# EagleIO.net
KiCad netlist of a schematic drawn in EAGLE
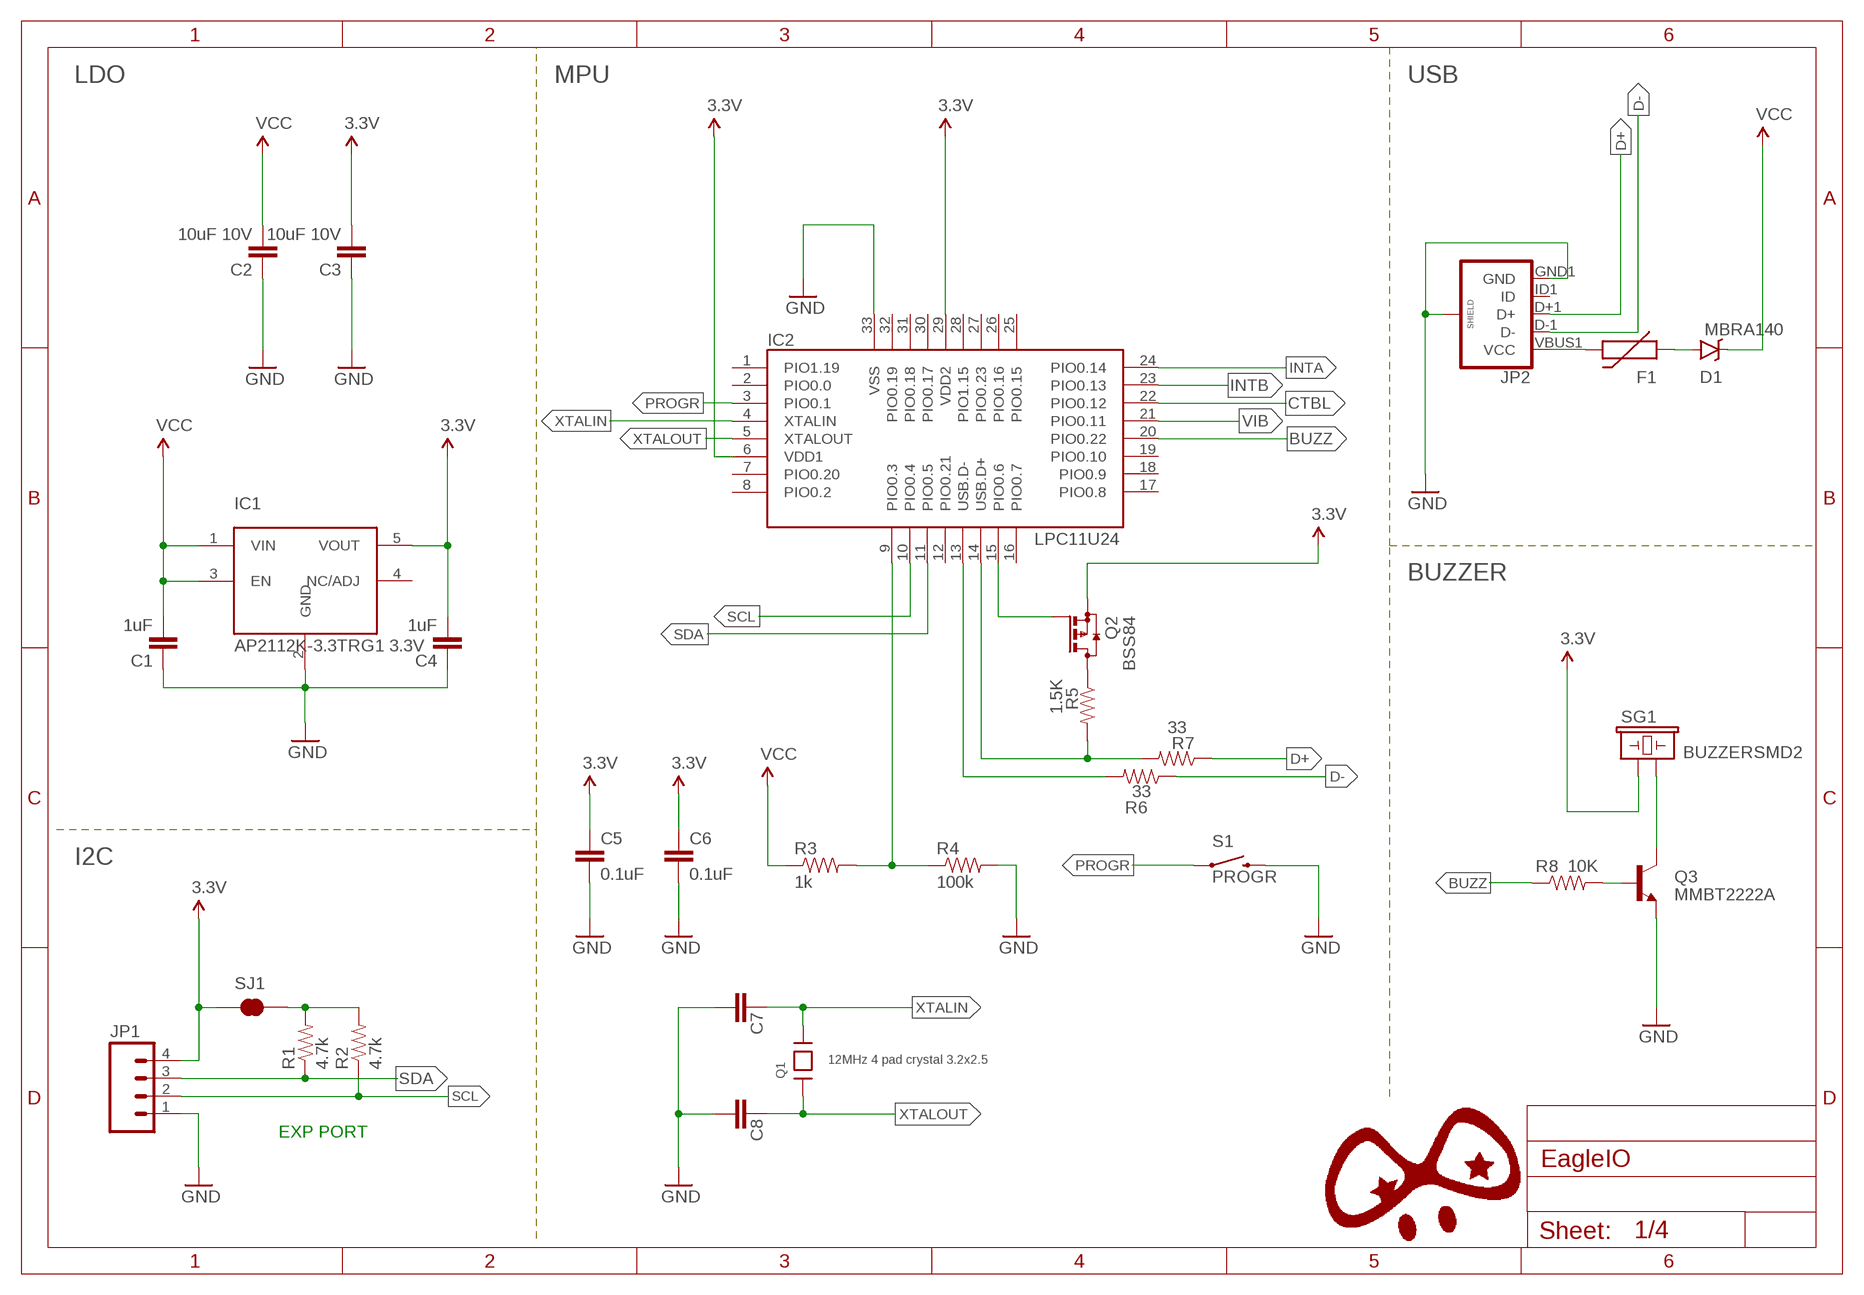
[diagram p0: schematic, sheet 1]
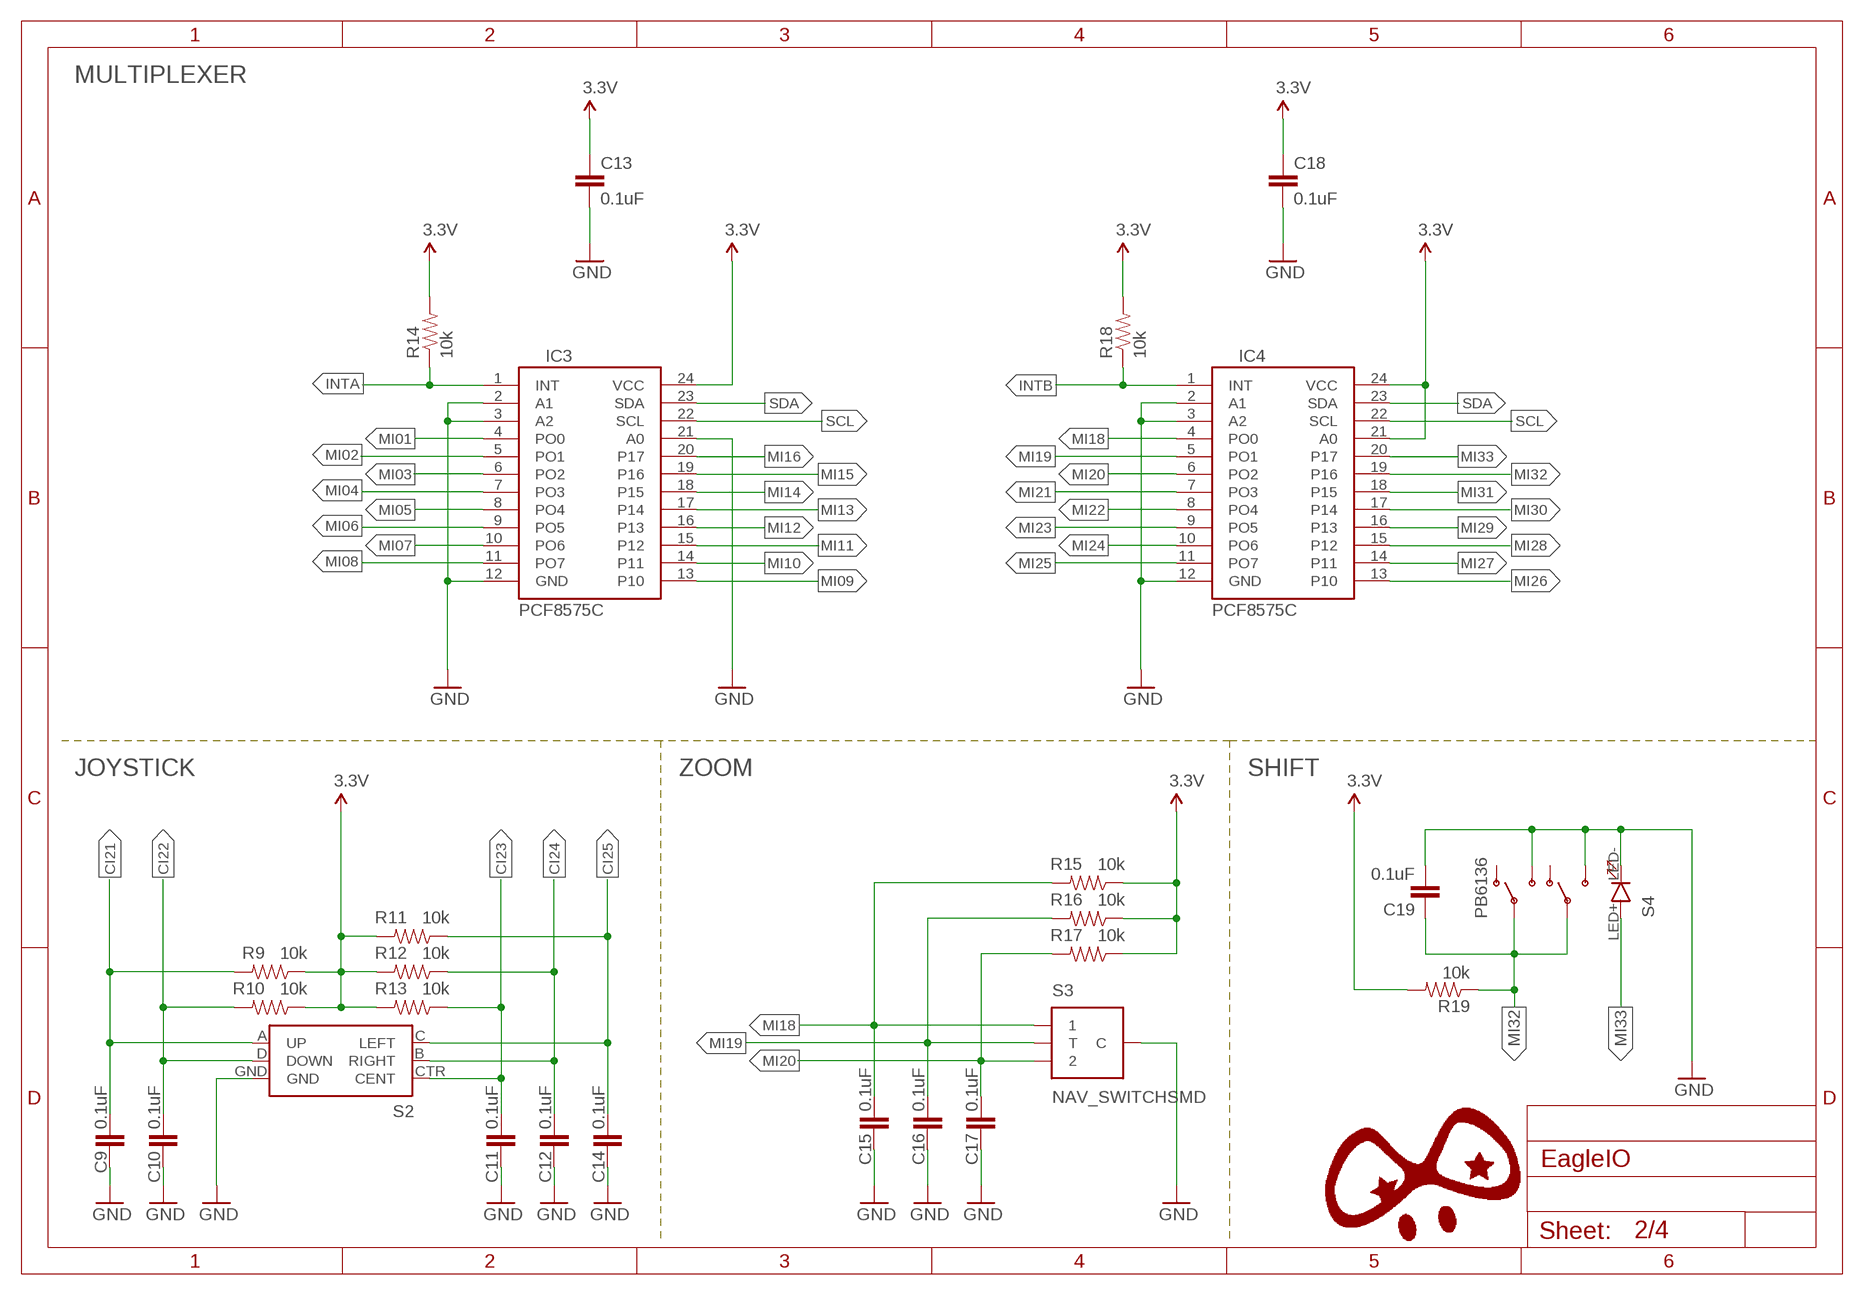
[diagram p1: schematic, sheet 2]
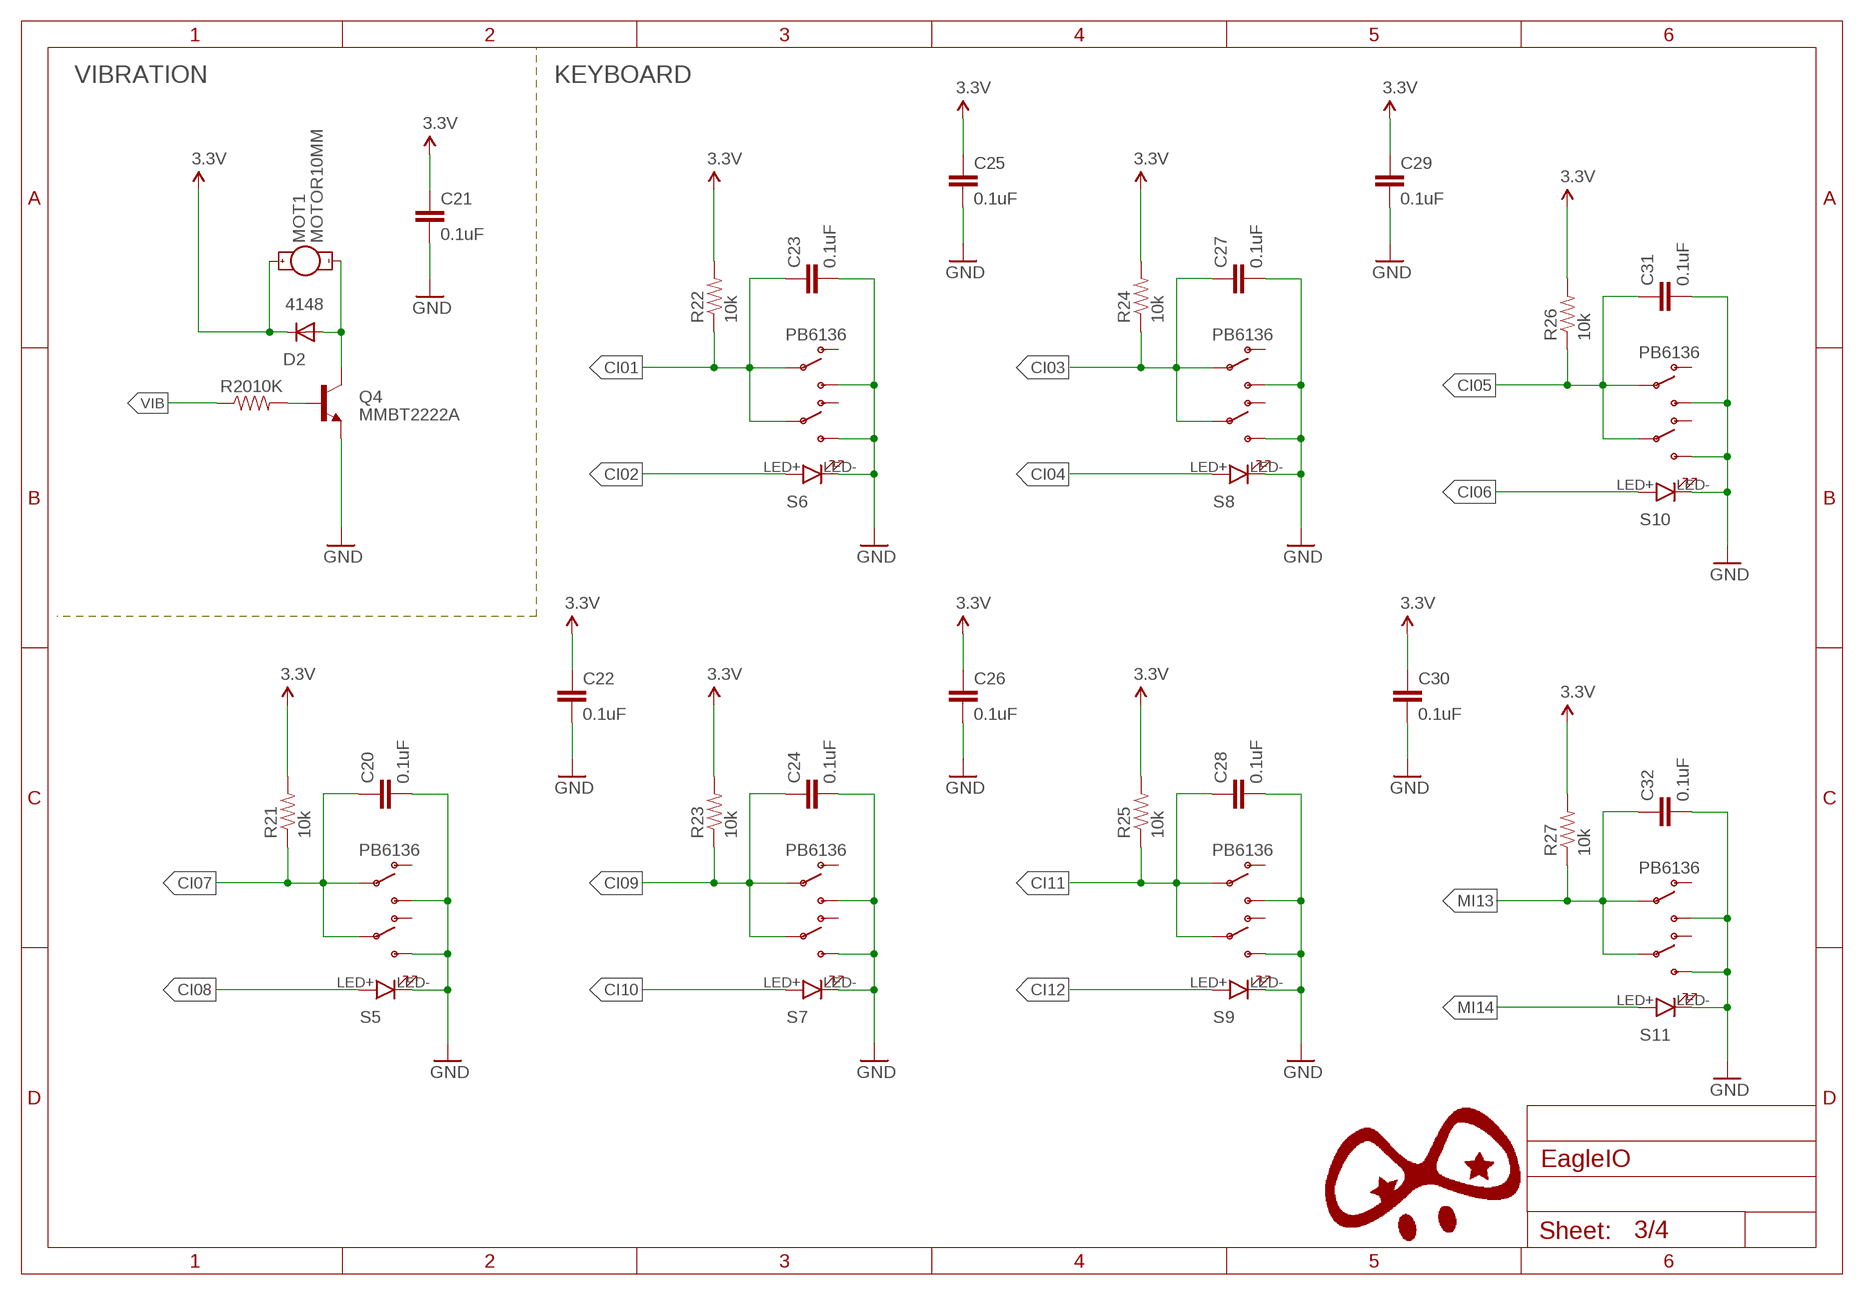
[diagram p2: schematic, sheet 3]
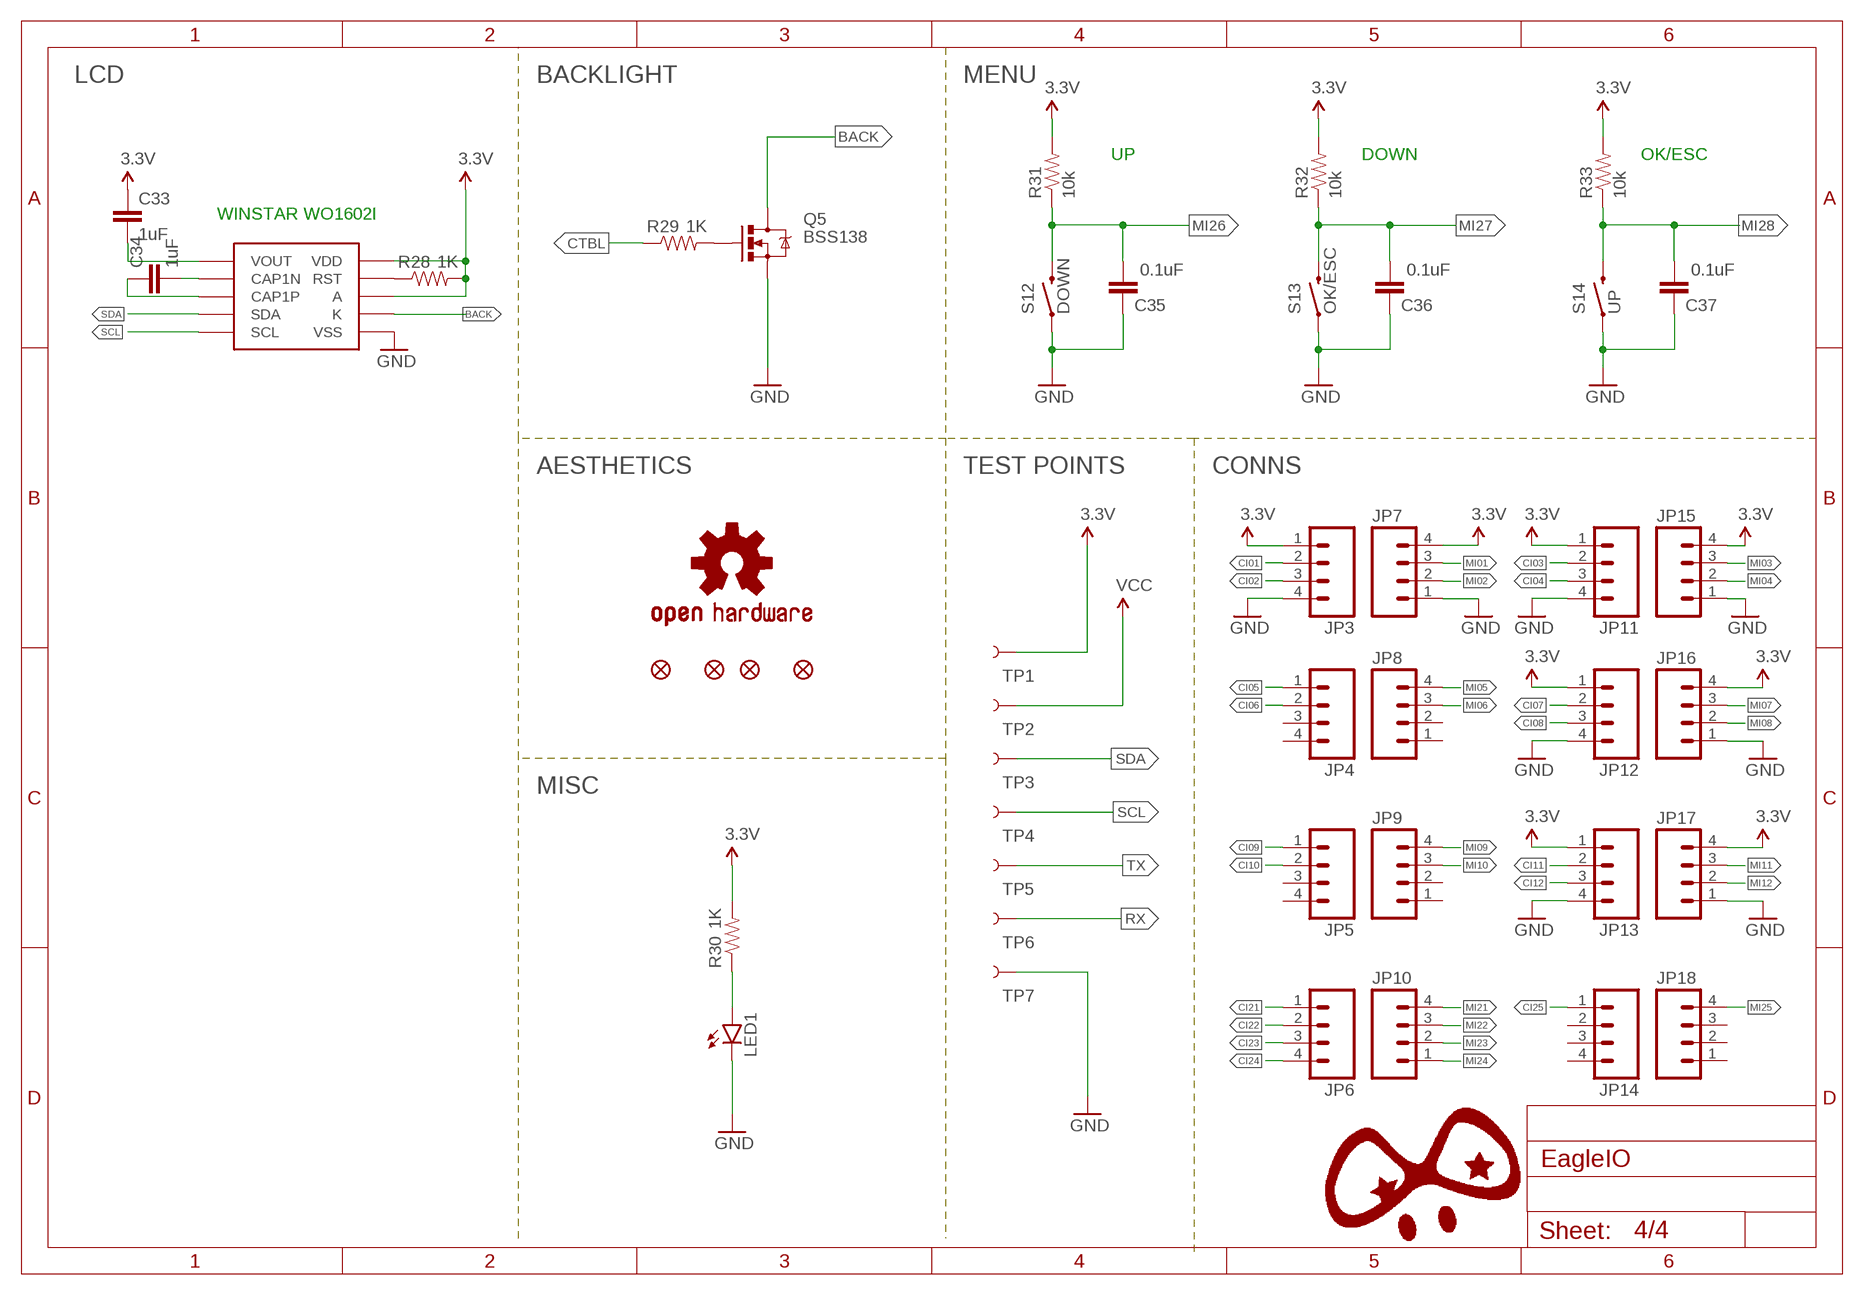
[diagram p3: schematic, sheet 4]

(export (version "E")
  (design (tool "Eeschema 10.0.6"))
  (components
    (comp (ref "C20")
      (value "0.1uF")
      (footprint "eagle-import:0402-CAP")
      (libsource (lib "eagle-import") (part "CAP0402-CAP"))
    )
    (comp (ref "C21")
      (value "0.1uF")
      (footprint "eagle-import:0402-CAP")
      (libsource (lib "eagle-import") (part "CAP0402-CAP"))
    )
    (comp (ref "C22")
      (value "0.1uF")
      (footprint "eagle-import:0402-CAP")
      (libsource (lib "eagle-import") (part "CAP0402-CAP"))
    )
    (comp (ref "C23")
      (value "0.1uF")
      (footprint "eagle-import:0402-CAP")
      (libsource (lib "eagle-import") (part "CAP0402-CAP"))
    )
    (comp (ref "C24")
      (value "0.1uF")
      (footprint "eagle-import:0402-CAP")
      (libsource (lib "eagle-import") (part "CAP0402-CAP"))
    )
    (comp (ref "C25")
      (value "0.1uF")
      (footprint "eagle-import:0402-CAP")
      (libsource (lib "eagle-import") (part "CAP0402-CAP"))
    )
    (comp (ref "C26")
      (value "0.1uF")
      (footprint "eagle-import:0402-CAP")
      (libsource (lib "eagle-import") (part "CAP0402-CAP"))
    )
    (comp (ref "C27")
      (value "0.1uF")
      (footprint "eagle-import:0402-CAP")
      (libsource (lib "eagle-import") (part "CAP0402-CAP"))
    )
    (comp (ref "C28")
      (value "0.1uF")
      (footprint "eagle-import:0402-CAP")
      (libsource (lib "eagle-import") (part "CAP0402-CAP"))
    )
    (comp (ref "C29")
      (value "0.1uF")
      (footprint "eagle-import:0402-CAP")
      (libsource (lib "eagle-import") (part "CAP0402-CAP"))
    )
    (comp (ref "C30")
      (value "0.1uF")
      (footprint "eagle-import:0402-CAP")
      (libsource (lib "eagle-import") (part "CAP0402-CAP"))
    )
    (comp (ref "C31")
      (value "0.1uF")
      (footprint "eagle-import:0402-CAP")
      (libsource (lib "eagle-import") (part "CAP0402-CAP"))
    )
    (comp (ref "C32")
      (value "0.1uF")
      (footprint "eagle-import:0402-CAP")
      (libsource (lib "eagle-import") (part "CAP0402-CAP"))
    )
    (comp (ref "D2")
      (value "4148")
      (footprint "eagle-import:MINIMELF")
      (libsource (lib "eagle-import") (part "DIODE-MINIMELF"))
    )
    (comp (ref "MOT1")
      (value "MOTOR10MM")
      (footprint "eagle-import:VIBE-MOTOR-10MM")
      (libsource (lib "eagle-import") (part "MOTOR10MM"))
    )
    (comp (ref "Q4")
      (value "MMBT2222A")
      (footprint "eagle-import:SOT23-3")
      (libsource (lib "eagle-import") (part "TRANSISTOR_NPNMMBT2222A"))
    )
    (comp (ref "R20")
      (value "10K")
      (footprint "eagle-import:0402-RES")
      (libsource (lib "eagle-import") (part "RESISTOR0402-RES"))
    )
    (comp (ref "R21")
      (value "10k")
      (footprint "eagle-import:0402-RES")
      (libsource (lib "eagle-import") (part "SparkFun-Passives_RESISTOR0402-RES"))
    )
    (comp (ref "R22")
      (value "10k")
      (footprint "eagle-import:0402-RES")
      (libsource (lib "eagle-import") (part "SparkFun-Passives_RESISTOR0402-RES"))
    )
    (comp (ref "R23")
      (value "10k")
      (footprint "eagle-import:0402-RES")
      (libsource (lib "eagle-import") (part "SparkFun-Passives_RESISTOR0402-RES"))
    )
    (comp (ref "R24")
      (value "10k")
      (footprint "eagle-import:0402-RES")
      (libsource (lib "eagle-import") (part "SparkFun-Passives_RESISTOR0402-RES"))
    )
    (comp (ref "R25")
      (value "10k")
      (footprint "eagle-import:0402-RES")
      (libsource (lib "eagle-import") (part "SparkFun-Passives_RESISTOR0402-RES"))
    )
    (comp (ref "R26")
      (value "10k")
      (footprint "eagle-import:0402-RES")
      (libsource (lib "eagle-import") (part "SparkFun-Passives_RESISTOR0402-RES"))
    )
    (comp (ref "R27")
      (value "10k")
      (footprint "eagle-import:0402-RES")
      (libsource (lib "eagle-import") (part "SparkFun-Passives_RESISTOR0402-RES"))
    )
    (comp (ref "S5")
      (value "PB6136")
      (footprint "eagle-import:PB6136")
      (libsource (lib "eagle-import") (part "PB6136"))
    )
    (comp (ref "S6")
      (value "PB6136")
      (footprint "eagle-import:PB6136")
      (libsource (lib "eagle-import") (part "PB6136"))
    )
    (comp (ref "S7")
      (value "PB6136")
      (footprint "eagle-import:PB6136")
      (libsource (lib "eagle-import") (part "PB6136"))
    )
    (comp (ref "S8")
      (value "PB6136")
      (footprint "eagle-import:PB6136")
      (libsource (lib "eagle-import") (part "PB6136"))
    )
    (comp (ref "S9")
      (value "PB6136")
      (footprint "eagle-import:PB6136")
      (libsource (lib "eagle-import") (part "PB6136"))
    )
    (comp (ref "S10")
      (value "PB6136")
      (footprint "eagle-import:PB6136")
      (libsource (lib "eagle-import") (part "PB6136"))
    )
    (comp (ref "S11")
      (value "PB6136")
      (footprint "eagle-import:PB6136")
      (libsource (lib "eagle-import") (part "PB6136"))
    )
    (comp (ref "C9")
      (value "0.1uF")
      (footprint "eagle-import:0402-CAP")
      (libsource (lib "eagle-import") (part "CAP0402-CAP"))
    )
    (comp (ref "C10")
      (value "0.1uF")
      (footprint "eagle-import:0402-CAP")
      (libsource (lib "eagle-import") (part "CAP0402-CAP"))
    )
    (comp (ref "C11")
      (value "0.1uF")
      (footprint "eagle-import:0402-CAP")
      (libsource (lib "eagle-import") (part "CAP0402-CAP"))
    )
    (comp (ref "C12")
      (value "0.1uF")
      (footprint "eagle-import:0402-CAP")
      (libsource (lib "eagle-import") (part "CAP0402-CAP"))
    )
    (comp (ref "C13")
      (value "0.1uF")
      (footprint "eagle-import:0402-CAP")
      (libsource (lib "eagle-import") (part "CAP0402-CAP"))
    )
    (comp (ref "C14")
      (value "0.1uF")
      (footprint "eagle-import:0402-CAP")
      (libsource (lib "eagle-import") (part "CAP0402-CAP"))
    )
    (comp (ref "C15")
      (value "0.1uF")
      (footprint "eagle-import:0402-CAP")
      (libsource (lib "eagle-import") (part "CAP0402-CAP"))
    )
    (comp (ref "C16")
      (value "0.1uF")
      (footprint "eagle-import:0402-CAP")
      (libsource (lib "eagle-import") (part "CAP0402-CAP"))
    )
    (comp (ref "C17")
      (value "0.1uF")
      (footprint "eagle-import:0402-CAP")
      (libsource (lib "eagle-import") (part "CAP0402-CAP"))
    )
    (comp (ref "C18")
      (value "0.1uF")
      (footprint "eagle-import:0402-CAP")
      (libsource (lib "eagle-import") (part "CAP0402-CAP"))
    )
    (comp (ref "C19")
      (value "0.1uF")
      (footprint "eagle-import:0402-CAP")
      (libsource (lib "eagle-import") (part "CAP0402-CAP"))
    )
    (comp (ref "IC3")
      (value "PCF8575C")
      (footprint "eagle-import:SO-24DW")
      (libsource (lib "eagle-import") (part "PCF8575C"))
    )
    (comp (ref "IC4")
      (value "PCF8575C")
      (footprint "eagle-import:SO-24DW")
      (libsource (lib "eagle-import") (part "PCF8575C"))
    )
    (comp (ref "R9")
      (value "10k")
      (footprint "eagle-import:0402-RES")
      (libsource (lib "eagle-import") (part "SparkFun-Passives_RESISTOR0402-RES"))
    )
    (comp (ref "R10")
      (value "10k")
      (footprint "eagle-import:0402-RES")
      (libsource (lib "eagle-import") (part "SparkFun-Passives_RESISTOR0402-RES"))
    )
    (comp (ref "R11")
      (value "10k")
      (footprint "eagle-import:0402-RES")
      (libsource (lib "eagle-import") (part "SparkFun-Passives_RESISTOR0402-RES"))
    )
    (comp (ref "R12")
      (value "10k")
      (footprint "eagle-import:0402-RES")
      (libsource (lib "eagle-import") (part "SparkFun-Passives_RESISTOR0402-RES"))
    )
    (comp (ref "R13")
      (value "10k")
      (footprint "eagle-import:0402-RES")
      (libsource (lib "eagle-import") (part "SparkFun-Passives_RESISTOR0402-RES"))
    )
    (comp (ref "R14")
      (value "10k")
      (footprint "eagle-import:0402-RES")
      (libsource (lib "eagle-import") (part "SparkFun-Passives_RESISTOR0402-RES"))
    )
    (comp (ref "R15")
      (value "10k")
      (footprint "eagle-import:0402-RES")
      (libsource (lib "eagle-import") (part "SparkFun-Passives_RESISTOR0402-RES"))
    )
    (comp (ref "R16")
      (value "10k")
      (footprint "eagle-import:0402-RES")
      (libsource (lib "eagle-import") (part "SparkFun-Passives_RESISTOR0402-RES"))
    )
    (comp (ref "R17")
      (value "10k")
      (footprint "eagle-import:0402-RES")
      (libsource (lib "eagle-import") (part "SparkFun-Passives_RESISTOR0402-RES"))
    )
    (comp (ref "R18")
      (value "10k")
      (footprint "eagle-import:0402-RES")
      (libsource (lib "eagle-import") (part "SparkFun-Passives_RESISTOR0402-RES"))
    )
    (comp (ref "R19")
      (value "10k")
      (footprint "eagle-import:0402-RES")
      (libsource (lib "eagle-import") (part "SparkFun-Passives_RESISTOR0402-RES"))
    )
    (comp (ref "S2")
      (value "JOYSTICK_MINI")
      (footprint "eagle-import:JOYSTICK_MINI")
      (libsource (lib "eagle-import") (part "JOYSTICK_MINI"))
    )
    (comp (ref "S3")
      (value "NAV_SWITCHSMD")
      (footprint "eagle-import:NAV_SWITCH")
      (libsource (lib "eagle-import") (part "NAV_SWITCHSMD"))
    )
    (comp (ref "S4")
      (value "PB6136")
      (footprint "eagle-import:PB6136")
      (libsource (lib "eagle-import") (part "PB6136"))
    )
    (comp (ref "C33")
      (value "1uF")
      (footprint "eagle-import:0402-CAP")
      (libsource (lib "eagle-import") (part "CAP0402-CAP"))
    )
    (comp (ref "C34")
      (value "1uF")
      (footprint "eagle-import:0402-CAP")
      (libsource (lib "eagle-import") (part "CAP0402-CAP"))
    )
    (comp (ref "C35")
      (value "0.1uF")
      (footprint "eagle-import:0402-CAP")
      (libsource (lib "eagle-import") (part "CAP0402-CAP"))
    )
    (comp (ref "C36")
      (value "0.1uF")
      (footprint "eagle-import:0402-CAP")
      (libsource (lib "eagle-import") (part "CAP0402-CAP"))
    )
    (comp (ref "C37")
      (value "0.1uF")
      (footprint "eagle-import:0402-CAP")
      (libsource (lib "eagle-import") (part "CAP0402-CAP"))
    )
    (comp (ref "FID1")
      (value "FIDUCIAL1X2")
      (footprint "eagle-import:FIDUCIAL-1X2")
      (libsource (lib "eagle-import") (part "FIDUCIAL1X2"))
    )
    (comp (ref "FID2")
      (value "FIDUCIAL1X2")
      (footprint "eagle-import:FIDUCIAL-1X2")
      (libsource (lib "eagle-import") (part "FIDUCIAL1X2"))
    )
    (comp (ref "FID3")
      (value "FIDUCIAL1X2")
      (footprint "eagle-import:FIDUCIAL-1X2")
      (libsource (lib "eagle-import") (part "FIDUCIAL1X2"))
    )
    (comp (ref "FID4")
      (value "FIDUCIAL1X2")
      (footprint "eagle-import:FIDUCIAL-1X2")
      (libsource (lib "eagle-import") (part "FIDUCIAL1X2"))
    )
    (comp (ref "JP3")
      (value "M041.27MM")
      (footprint "eagle-import:1X04-1.27MM")
      (libsource (lib "eagle-import") (part "M041.27MM"))
    )
    (comp (ref "JP4")
      (value "M041.27MM")
      (footprint "eagle-import:1X04-1.27MM")
      (libsource (lib "eagle-import") (part "M041.27MM"))
    )
    (comp (ref "JP5")
      (value "M041.27MM")
      (footprint "eagle-import:1X04-1.27MM")
      (libsource (lib "eagle-import") (part "M041.27MM"))
    )
    (comp (ref "JP6")
      (value "M041.27MM")
      (footprint "eagle-import:1X04-1.27MM")
      (libsource (lib "eagle-import") (part "M041.27MM"))
    )
    (comp (ref "JP7")
      (value "M041.27MM")
      (footprint "eagle-import:1X04-1.27MM")
      (libsource (lib "eagle-import") (part "M041.27MM"))
    )
    (comp (ref "JP8")
      (value "M041.27MM")
      (footprint "eagle-import:1X04-1.27MM")
      (libsource (lib "eagle-import") (part "M041.27MM"))
    )
    (comp (ref "JP9")
      (value "M041.27MM")
      (footprint "eagle-import:1X04-1.27MM")
      (libsource (lib "eagle-import") (part "M041.27MM"))
    )
    (comp (ref "JP10")
      (value "M041.27MM")
      (footprint "eagle-import:1X04-1.27MM")
      (libsource (lib "eagle-import") (part "M041.27MM"))
    )
    (comp (ref "JP11")
      (value "M041.27MM")
      (footprint "eagle-import:1X04-1.27MM")
      (libsource (lib "eagle-import") (part "M041.27MM"))
    )
    (comp (ref "JP12")
      (value "M041.27MM")
      (footprint "eagle-import:1X04-1.27MM")
      (libsource (lib "eagle-import") (part "M041.27MM"))
    )
    (comp (ref "JP13")
      (value "M041.27MM")
      (footprint "eagle-import:1X04-1.27MM")
      (libsource (lib "eagle-import") (part "M041.27MM"))
    )
    (comp (ref "JP14")
      (value "M041.27MM")
      (footprint "eagle-import:1X04-1.27MM")
      (libsource (lib "eagle-import") (part "M041.27MM"))
    )
    (comp (ref "JP15")
      (value "M041.27MM")
      (footprint "eagle-import:1X04-1.27MM")
      (libsource (lib "eagle-import") (part "M041.27MM"))
    )
    (comp (ref "JP16")
      (value "M041.27MM")
      (footprint "eagle-import:1X04-1.27MM")
      (libsource (lib "eagle-import") (part "M041.27MM"))
    )
    (comp (ref "JP17")
      (value "M041.27MM")
      (footprint "eagle-import:1X04-1.27MM")
      (libsource (lib "eagle-import") (part "M041.27MM"))
    )
    (comp (ref "JP18")
      (value "M041.27MM")
      (footprint "eagle-import:1X04-1.27MM")
      (libsource (lib "eagle-import") (part "M041.27MM"))
    )
    (comp (ref "LCD1")
      (value "WINSTAR_WO1602I")
      (footprint "eagle-import:WINSTAR_WO1602I")
      (libsource (lib "eagle-import") (part "WINSTAR_WO1602I"))
    )
    (comp (ref "LED1")
      (value "LED0603")
      (footprint "eagle-import:LED-0603")
      (libsource (lib "eagle-import") (part "LED0603"))
    )
    (comp (ref "LOGO1")
      (value "OSHW-LOGOS")
      (footprint "eagle-import:OSHW-LOGO-S")
      (libsource (lib "eagle-import") (part "OSHW-LOGOS"))
    )
    (comp (ref "Q5")
      (value "BSS138")
      (footprint "eagle-import:SOT323")
      (libsource (lib "eagle-import") (part "MOSFET-NCHANNEL2N7002PW"))
    )
    (comp (ref "R28")
      (value "1K")
      (footprint "eagle-import:0402-RES")
      (libsource (lib "eagle-import") (part "RESISTOR0402-RES"))
    )
    (comp (ref "R29")
      (value "1K")
      (footprint "eagle-import:0402-RES")
      (libsource (lib "eagle-import") (part "RESISTOR0402-RES"))
    )
    (comp (ref "R30")
      (value "1K")
      (footprint "eagle-import:0402-RES")
      (libsource (lib "eagle-import") (part "RESISTOR0402-RES"))
    )
    (comp (ref "R31")
      (value "10k")
      (footprint "eagle-import:0402-RES")
      (libsource (lib "eagle-import") (part "SparkFun-Passives_RESISTOR0402-RES"))
    )
    (comp (ref "R32")
      (value "10k")
      (footprint "eagle-import:0402-RES")
      (libsource (lib "eagle-import") (part "SparkFun-Passives_RESISTOR0402-RES"))
    )
    (comp (ref "R33")
      (value "10k")
      (footprint "eagle-import:0402-RES")
      (libsource (lib "eagle-import") (part "SparkFun-Passives_RESISTOR0402-RES"))
    )
    (comp (ref "S12")
      (value "DOWN")
      (footprint "eagle-import:TACTILE-SWITCH-1101NE")
      (libsource (lib "eagle-import") (part "SWITCH-MOMENTARY-2SMD-1101NE"))
    )
    (comp (ref "S13")
      (value "OK/ESC")
      (footprint "eagle-import:TACTILE-SWITCH-1101NE")
      (libsource (lib "eagle-import") (part "SWITCH-MOMENTARY-2SMD-1101NE"))
    )
    (comp (ref "S14")
      (value "UP")
      (footprint "eagle-import:TACTILE-SWITCH-1101NE")
      (libsource (lib "eagle-import") (part "SWITCH-MOMENTARY-2SMD-1101NE"))
    )
    (comp (ref "TP1")
      (value "TEST-POINT3X5")
      (footprint "eagle-import:PAD.03X.05")
      (libsource (lib "eagle-import") (part "TEST-POINT3X5"))
    )
    (comp (ref "TP2")
      (value "TEST-POINT3X5")
      (footprint "eagle-import:PAD.03X.05")
      (libsource (lib "eagle-import") (part "TEST-POINT3X5"))
    )
    (comp (ref "TP3")
      (value "TEST-POINT3X5")
      (footprint "eagle-import:PAD.03X.05")
      (libsource (lib "eagle-import") (part "TEST-POINT3X5"))
    )
    (comp (ref "TP4")
      (value "TEST-POINT3X5")
      (footprint "eagle-import:PAD.03X.05")
      (libsource (lib "eagle-import") (part "TEST-POINT3X5"))
    )
    (comp (ref "TP5")
      (value "TEST-POINT3X5")
      (footprint "eagle-import:PAD.03X.05")
      (libsource (lib "eagle-import") (part "TEST-POINT3X5"))
    )
    (comp (ref "TP6")
      (value "TEST-POINT3X5")
      (footprint "eagle-import:PAD.03X.05")
      (libsource (lib "eagle-import") (part "TEST-POINT3X5"))
    )
    (comp (ref "TP7")
      (value "TEST-POINT3X5")
      (footprint "eagle-import:PAD.03X.05")
      (libsource (lib "eagle-import") (part "TEST-POINT3X5"))
    )
    (comp (ref "C1")
      (value "1uF")
      (footprint "eagle-import:0402-CAP")
      (libsource (lib "eagle-import") (part "CAP0402-CAP"))
    )
    (comp (ref "C2")
      (value "10uF 10V")
      (footprint "eagle-import:0402-CAP")
      (libsource (lib "eagle-import") (part "CAP0402-CAP"))
    )
    (comp (ref "C3")
      (value "10uF 10V")
      (footprint "eagle-import:0402-CAP")
      (libsource (lib "eagle-import") (part "CAP0402-CAP"))
    )
    (comp (ref "C4")
      (value "1uF")
      (footprint "eagle-import:0402-CAP")
      (libsource (lib "eagle-import") (part "CAP0402-CAP"))
    )
    (comp (ref "C5")
      (value "0.1uF")
      (footprint "eagle-import:0402-CAP")
      (libsource (lib "eagle-import") (part "CAP0402-CAP"))
    )
    (comp (ref "C6")
      (value "0.1uF")
      (footprint "eagle-import:0402-CAP")
      (libsource (lib "eagle-import") (part "CAP0402-CAP"))
    )
    (comp (ref "C7")
      (value "27pF")
      (footprint "eagle-import:0402-CAP")
      (libsource (lib "eagle-import") (part "CAP0402-CAP"))
    )
    (comp (ref "C8")
      (value "27pF")
      (footprint "eagle-import:0402-CAP")
      (libsource (lib "eagle-import") (part "CAP0402-CAP"))
    )
    (comp (ref "D1")
      (value "MBRA140")
      (footprint "eagle-import:SMA-DIODE")
      (libsource (lib "eagle-import") (part "MBRA140"))
    )
    (comp (ref "F1")
      (value "PTC0603")
      (footprint "eagle-import:0603")
      (libsource (lib "eagle-import") (part "PTC0603"))
    )
    (comp (ref "IC1")
      (value "AP2112K-3.3TRG1 3.3V")
      (footprint "eagle-import:SOT23-5")
      (libsource (lib "eagle-import") (part "5PIN_REG"))
    )
    (comp (ref "IC2")
      (value "LPC11U24")
      (footprint "eagle-import:HVQFN33_5X5MM")
      (libsource (lib "eagle-import") (part "LPC11U2X_HVQFN33(5X5)"))
    )
    (comp (ref "JP1")
      (value "M04LONGPADS")
      (footprint "eagle-import:1X04_LONGPADS")
      (libsource (lib "eagle-import") (part "M04LONGPADS"))
    )
    (comp (ref "JP2")
      (value "USB_MICROB_PLUGCONN-11752")
      (footprint "eagle-import:USB-B-MICRO-SMD_V03")
      (libsource (lib "eagle-import") (part "USB_MICROB_PLUGCONN-11752"))
    )
    (comp (ref "Q1")
      (value "12MHz 4 pad crystal 3.2x2.5")
      (footprint "eagle-import:CRYSTAL_3.2X2.5")
      (libsource (lib "eagle-import") (part "CRYSTAL3.2X2.5"))
    )
    (comp (ref "Q2")
      (value "BSS84")
      (footprint "eagle-import:SOT23")
      (libsource (lib "eagle-import") (part "BSS84"))
    )
    (comp (ref "Q3")
      (value "MMBT2222A")
      (footprint "eagle-import:SOT23-3")
      (libsource (lib "eagle-import") (part "TRANSISTOR_NPNMMBT2222A"))
    )
    (comp (ref "R1")
      (value "4.7k")
      (footprint "eagle-import:0402-RES")
      (libsource (lib "eagle-import") (part "SparkFun-Passives_RESISTOR0402-RES"))
    )
    (comp (ref "R2")
      (value "4.7k")
      (footprint "eagle-import:0402-RES")
      (libsource (lib "eagle-import") (part "SparkFun-Passives_RESISTOR0402-RES"))
    )
    (comp (ref "R3")
      (value "1k")
      (footprint "eagle-import:0402-RES")
      (libsource (lib "eagle-import") (part "SparkFun-Passives_RESISTOR0402-RES"))
    )
    (comp (ref "R4")
      (value "100k")
      (footprint "eagle-import:0402-RES")
      (libsource (lib "eagle-import") (part "SparkFun-Passives_RESISTOR0402-RES"))
    )
    (comp (ref "R5")
      (value "1.5K")
      (footprint "eagle-import:0402-RES")
      (libsource (lib "eagle-import") (part "SparkFun-Passives_RESISTOR0402-RES"))
    )
    (comp (ref "R6")
      (value "33")
      (footprint "eagle-import:0402-RES")
      (libsource (lib "eagle-import") (part "SparkFun-Passives_RESISTOR0402-RES"))
    )
    (comp (ref "R7")
      (value "33")
      (footprint "eagle-import:0402-RES")
      (libsource (lib "eagle-import") (part "SparkFun-Passives_RESISTOR0402-RES"))
    )
    (comp (ref "R8")
      (value "10K")
      (footprint "eagle-import:0402-RES")
      (libsource (lib "eagle-import") (part "RESISTOR0402-RES"))
    )
    (comp (ref "S1")
      (value "PROGR")
      (footprint "eagle-import:TACTILE-SWITCH-1101NE")
      (libsource (lib "eagle-import") (part "SWITCH-MOMENTARY-2SMD-1101NE"))
    )
    (comp (ref "SG1")
      (value "BUZZERSMD2")
      (footprint "eagle-import:BUZZER-CCV")
      (libsource (lib "eagle-import") (part "BUZZERSMD2"))
    )
    (comp (ref "SJ1")
      (value "JUMPER-PAD-2-NC_BY_TRACE")
      (footprint "eagle-import:PAD-JUMPER-2-NC_BY_TRACE_YES_SILK")
      (libsource (lib "eagle-import") (part "JUMPER-PAD-2-NC_BY_TRACE"))
    )
  )
  (nets
    (net (code "1") (name "3.3V") (class "Default")
      (node (ref "C13") (pin "1") (pinfunction "1_1") (pintype "passive"))
      (node (ref "C18") (pin "1") (pinfunction "1_1") (pintype "passive"))
      (node (ref "C21") (pin "1") (pinfunction "1_1") (pintype "passive"))
      (node (ref "C22") (pin "1") (pinfunction "1_1") (pintype "passive"))
      (node (ref "C25") (pin "1") (pinfunction "1_1") (pintype "passive"))
      (node (ref "C26") (pin "1") (pinfunction "1_1") (pintype "passive"))
      (node (ref "C29") (pin "1") (pinfunction "1_1") (pintype "passive"))
      (node (ref "C3") (pin "2") (pinfunction "2_2") (pintype "passive"))
      (node (ref "C30") (pin "1") (pinfunction "1_1") (pintype "passive"))
      (node (ref "C33") (pin "1") (pinfunction "1_1") (pintype "passive"))
      (node (ref "C4") (pin "2") (pinfunction "2_2") (pintype "passive"))
      (node (ref "C5") (pin "1") (pinfunction "1_1") (pintype "passive"))
      (node (ref "C6") (pin "1") (pinfunction "1_1") (pintype "passive"))
      (node (ref "D2") (pin "C") (pinfunction "C_C") (pintype "passive"))
      (node (ref "IC1") (pin "5") (pinfunction "VOUT_5") (pintype "bidirectional"))
      (node (ref "IC2") (pin "29") (pinfunction "VDD2_29") (pintype "bidirectional"))
      (node (ref "IC2") (pin "6") (pinfunction "VDD1_6") (pintype "bidirectional"))
      (node (ref "IC3") (pin "24") (pinfunction "VCC_24") (pintype "bidirectional"))
      (node (ref "IC4") (pin "21") (pinfunction "A0_21") (pintype "bidirectional"))
      (node (ref "IC4") (pin "24") (pinfunction "VCC_24") (pintype "bidirectional"))
      (node (ref "JP1") (pin "4") (pinfunction "4_4") (pintype "passive"))
      (node (ref "JP11") (pin "1") (pinfunction "1_1") (pintype "passive"))
      (node (ref "JP12") (pin "1") (pinfunction "1_1") (pintype "passive"))
      (node (ref "JP13") (pin "1") (pinfunction "1_1") (pintype "passive"))
      (node (ref "JP15") (pin "4") (pinfunction "4_4") (pintype "passive"))
      (node (ref "JP16") (pin "4") (pinfunction "4_4") (pintype "passive"))
      (node (ref "JP17") (pin "4") (pinfunction "4_4") (pintype "passive"))
      (node (ref "JP3") (pin "1") (pinfunction "1_1") (pintype "passive"))
      (node (ref "JP7") (pin "4") (pinfunction "4_4") (pintype "passive"))
      (node (ref "LCD1") (pin "AB") (pinfunction "A_AB") (pintype "bidirectional"))
      (node (ref "LCD1") (pin "AT") (pinfunction "A_AT") (pintype "bidirectional"))
      (node (ref "LCD1") (pin "VDD") (pinfunction "VDD_VDD") (pintype "bidirectional"))
      (node (ref "MOT1") (pin "+") (pinfunction "+_+") (pintype "bidirectional"))
      (node (ref "Q2") (pin "2") (pinfunction "S_2") (pintype "passive"))
      (node (ref "R10") (pin "1") (pinfunction "1_1") (pintype "passive"))
      (node (ref "R11") (pin "2") (pinfunction "2_2") (pintype "passive"))
      (node (ref "R12") (pin "2") (pinfunction "2_2") (pintype "passive"))
      (node (ref "R13") (pin "2") (pinfunction "2_2") (pintype "passive"))
      (node (ref "R14") (pin "2") (pinfunction "2_2") (pintype "passive"))
      (node (ref "R15") (pin "1") (pinfunction "1_1") (pintype "passive"))
      (node (ref "R16") (pin "1") (pinfunction "1_1") (pintype "passive"))
      (node (ref "R17") (pin "1") (pinfunction "1_1") (pintype "passive"))
      (node (ref "R18") (pin "2") (pinfunction "2_2") (pintype "passive"))
      (node (ref "R19") (pin "2") (pinfunction "2_2") (pintype "passive"))
      (node (ref "R21") (pin "2") (pinfunction "2_2") (pintype "passive"))
      (node (ref "R22") (pin "2") (pinfunction "2_2") (pintype "passive"))
      (node (ref "R23") (pin "2") (pinfunction "2_2") (pintype "passive"))
      (node (ref "R24") (pin "2") (pinfunction "2_2") (pintype "passive"))
      (node (ref "R25") (pin "2") (pinfunction "2_2") (pintype "passive"))
      (node (ref "R26") (pin "2") (pinfunction "2_2") (pintype "passive"))
      (node (ref "R27") (pin "2") (pinfunction "2_2") (pintype "passive"))
      (node (ref "R28") (pin "2") (pinfunction "2_2") (pintype "passive"))
      (node (ref "R30") (pin "2") (pinfunction "2_2") (pintype "passive"))
      (node (ref "R31") (pin "2") (pinfunction "2_2") (pintype "passive"))
      (node (ref "R32") (pin "2") (pinfunction "2_2") (pintype "passive"))
      (node (ref "R33") (pin "2") (pinfunction "2_2") (pintype "passive"))
      (node (ref "R9") (pin "1") (pinfunction "1_1") (pintype "passive"))
      (node (ref "SG1") (pin "+") (pinfunction "1_+") (pintype "passive"))
      (node (ref "SJ1") (pin "1") (pinfunction "1_1") (pintype "passive"))
      (node (ref "TP1") (pin "P$1") (pinfunction "1_P$1") (pintype "bidirectional"))
    )
    (net (code "2") (name "BACK") (class "Default")
      (node (ref "LCD1") (pin "KB") (pinfunction "K_KB") (pintype "bidirectional"))
      (node (ref "LCD1") (pin "KT") (pinfunction "K_KT") (pintype "bidirectional"))
      (node (ref "Q5") (pin "3") (pinfunction "D_3") (pintype "passive"))
    )
    (net (code "3") (name "BUZZ") (class "Default")
      (node (ref "IC2") (pin "20") (pinfunction "PIO0.22_20") (pintype "bidirectional"))
      (node (ref "R8") (pin "1") (pinfunction "1_1") (pintype "passive"))
    )
    (net (code "4") (name "CI01") (class "Default")
      (node (ref "C23") (pin "1") (pinfunction "1_1") (pintype "passive"))
      (node (ref "JP3") (pin "2") (pinfunction "2_2") (pintype "passive"))
      (node (ref "R22") (pin "1") (pinfunction "1_1") (pintype "passive"))
      (node (ref "S6") (pin "C1") (pinfunction "P_C1") (pintype "passive"))
      (node (ref "S6") (pin "C2") (pinfunction "P1_C2") (pintype "passive"))
    )
    (net (code "5") (name "CI02") (class "Default")
      (node (ref "JP3") (pin "3") (pinfunction "3_3") (pintype "passive"))
      (node (ref "S6") (pin "LED+") (pinfunction "1_LED+") (pintype "passive"))
    )
    (net (code "6") (name "CI03") (class "Default")
      (node (ref "C27") (pin "1") (pinfunction "1_1") (pintype "passive"))
      (node (ref "JP11") (pin "2") (pinfunction "2_2") (pintype "passive"))
      (node (ref "R24") (pin "1") (pinfunction "1_1") (pintype "passive"))
      (node (ref "S8") (pin "C1") (pinfunction "P_C1") (pintype "passive"))
      (node (ref "S8") (pin "C2") (pinfunction "P1_C2") (pintype "passive"))
    )
    (net (code "7") (name "CI04") (class "Default")
      (node (ref "JP11") (pin "3") (pinfunction "3_3") (pintype "passive"))
      (node (ref "S8") (pin "LED+") (pinfunction "1_LED+") (pintype "passive"))
    )
    (net (code "8") (name "CI05") (class "Default")
      (node (ref "C31") (pin "1") (pinfunction "1_1") (pintype "passive"))
      (node (ref "JP4") (pin "1") (pinfunction "1_1") (pintype "passive"))
      (node (ref "R26") (pin "1") (pinfunction "1_1") (pintype "passive"))
      (node (ref "S10") (pin "C1") (pinfunction "P_C1") (pintype "passive"))
      (node (ref "S10") (pin "C2") (pinfunction "P1_C2") (pintype "passive"))
    )
    (net (code "9") (name "CI06") (class "Default")
      (node (ref "JP4") (pin "2") (pinfunction "2_2") (pintype "passive"))
      (node (ref "S10") (pin "LED+") (pinfunction "1_LED+") (pintype "passive"))
    )
    (net (code "10") (name "CI07") (class "Default")
      (node (ref "C20") (pin "1") (pinfunction "1_1") (pintype "passive"))
      (node (ref "JP12") (pin "2") (pinfunction "2_2") (pintype "passive"))
      (node (ref "R21") (pin "1") (pinfunction "1_1") (pintype "passive"))
      (node (ref "S5") (pin "C1") (pinfunction "P_C1") (pintype "passive"))
      (node (ref "S5") (pin "C2") (pinfunction "P1_C2") (pintype "passive"))
    )
    (net (code "11") (name "CI08") (class "Default")
      (node (ref "JP12") (pin "3") (pinfunction "3_3") (pintype "passive"))
      (node (ref "S5") (pin "LED+") (pinfunction "1_LED+") (pintype "passive"))
    )
    (net (code "12") (name "CI09") (class "Default")
      (node (ref "C24") (pin "1") (pinfunction "1_1") (pintype "passive"))
      (node (ref "JP5") (pin "1") (pinfunction "1_1") (pintype "passive"))
      (node (ref "R23") (pin "1") (pinfunction "1_1") (pintype "passive"))
      (node (ref "S7") (pin "C1") (pinfunction "P_C1") (pintype "passive"))
      (node (ref "S7") (pin "C2") (pinfunction "P1_C2") (pintype "passive"))
    )
    (net (code "13") (name "CI10") (class "Default")
      (node (ref "JP5") (pin "2") (pinfunction "2_2") (pintype "passive"))
      (node (ref "S7") (pin "LED+") (pinfunction "1_LED+") (pintype "passive"))
    )
    (net (code "14") (name "CI11") (class "Default")
      (node (ref "C28") (pin "1") (pinfunction "1_1") (pintype "passive"))
      (node (ref "JP13") (pin "2") (pinfunction "2_2") (pintype "passive"))
      (node (ref "R25") (pin "1") (pinfunction "1_1") (pintype "passive"))
      (node (ref "S9") (pin "C1") (pinfunction "P_C1") (pintype "passive"))
      (node (ref "S9") (pin "C2") (pinfunction "P1_C2") (pintype "passive"))
    )
    (net (code "15") (name "CI12") (class "Default")
      (node (ref "JP13") (pin "3") (pinfunction "3_3") (pintype "passive"))
      (node (ref "S9") (pin "LED+") (pinfunction "1_LED+") (pintype "passive"))
    )
    (net (code "16") (name "CI21") (class "Default")
      (node (ref "C9") (pin "2") (pinfunction "2_2") (pintype "passive"))
      (node (ref "JP6") (pin "1") (pinfunction "1_1") (pintype "passive"))
      (node (ref "R9") (pin "2") (pinfunction "2_2") (pintype "passive"))
      (node (ref "S2") (pin "A") (pinfunction "UP_A") (pintype "bidirectional"))
    )
    (net (code "17") (name "CI22") (class "Default")
      (node (ref "C10") (pin "2") (pinfunction "2_2") (pintype "passive"))
      (node (ref "JP6") (pin "2") (pinfunction "2_2") (pintype "passive"))
      (node (ref "R10") (pin "2") (pinfunction "2_2") (pintype "passive"))
      (node (ref "S2") (pin "D") (pinfunction "DOWN_D") (pintype "bidirectional"))
    )
    (net (code "18") (name "CI23") (class "Default")
      (node (ref "C11") (pin "2") (pinfunction "2_2") (pintype "passive"))
      (node (ref "JP6") (pin "3") (pinfunction "3_3") (pintype "passive"))
      (node (ref "R13") (pin "1") (pinfunction "1_1") (pintype "passive"))
      (node (ref "S2") (pin "CTR") (pinfunction "CENT_CTR") (pintype "bidirectional"))
    )
    (net (code "19") (name "CI24") (class "Default")
      (node (ref "C12") (pin "2") (pinfunction "2_2") (pintype "passive"))
      (node (ref "JP6") (pin "4") (pinfunction "4_4") (pintype "passive"))
      (node (ref "R12") (pin "1") (pinfunction "1_1") (pintype "passive"))
      (node (ref "S2") (pin "B") (pinfunction "RIGHT_B") (pintype "bidirectional"))
    )
    (net (code "20") (name "CI25") (class "Default")
      (node (ref "C14") (pin "2") (pinfunction "2_2") (pintype "passive"))
      (node (ref "JP14") (pin "1") (pinfunction "1_1") (pintype "passive"))
      (node (ref "R11") (pin "1") (pinfunction "1_1") (pintype "passive"))
      (node (ref "S2") (pin "C") (pinfunction "LEFT_C") (pintype "bidirectional"))
    )
    (net (code "21") (name "CTBL") (class "Default")
      (node (ref "IC2") (pin "22") (pinfunction "PIO0.12_22") (pintype "bidirectional"))
      (node (ref "R29") (pin "1") (pinfunction "1_1") (pintype "passive"))
    )
    (net (code "22") (name "D+") (class "Default")
      (node (ref "JP2") (pin "D+1") (pinfunction "D+_D+1") (pintype "bidirectional"))
      (node (ref "R7") (pin "1") (pinfunction "1_1") (pintype "passive"))
    )
    (net (code "23") (name "D-") (class "Default")
      (node (ref "JP2") (pin "D-1") (pinfunction "D-_D-1") (pintype "bidirectional"))
      (node (ref "R6") (pin "1") (pinfunction "1_1") (pintype "passive"))
    )
    (net (code "24") (name "GND") (class "Default")
      (node (ref "C1") (pin "1") (pinfunction "1_1") (pintype "passive"))
      (node (ref "C10") (pin "1") (pinfunction "1_1") (pintype "passive"))
      (node (ref "C11") (pin "1") (pinfunction "1_1") (pintype "passive"))
      (node (ref "C12") (pin "1") (pinfunction "1_1") (pintype "passive"))
      (node (ref "C13") (pin "2") (pinfunction "2_2") (pintype "passive"))
      (node (ref "C14") (pin "1") (pinfunction "1_1") (pintype "passive"))
      (node (ref "C15") (pin "1") (pinfunction "1_1") (pintype "passive"))
      (node (ref "C16") (pin "1") (pinfunction "1_1") (pintype "passive"))
      (node (ref "C17") (pin "1") (pinfunction "1_1") (pintype "passive"))
      (node (ref "C18") (pin "2") (pinfunction "2_2") (pintype "passive"))
      (node (ref "C19") (pin "2") (pinfunction "2_2") (pintype "passive"))
      (node (ref "C2") (pin "1") (pinfunction "1_1") (pintype "passive"))
      (node (ref "C20") (pin "2") (pinfunction "2_2") (pintype "passive"))
      (node (ref "C21") (pin "2") (pinfunction "2_2") (pintype "passive"))
      (node (ref "C22") (pin "2") (pinfunction "2_2") (pintype "passive"))
      (node (ref "C23") (pin "2") (pinfunction "2_2") (pintype "passive"))
      (node (ref "C24") (pin "2") (pinfunction "2_2") (pintype "passive"))
      (node (ref "C25") (pin "2") (pinfunction "2_2") (pintype "passive"))
      (node (ref "C26") (pin "2") (pinfunction "2_2") (pintype "passive"))
      (node (ref "C27") (pin "2") (pinfunction "2_2") (pintype "passive"))
      (node (ref "C28") (pin "2") (pinfunction "2_2") (pintype "passive"))
      (node (ref "C29") (pin "2") (pinfunction "2_2") (pintype "passive"))
      (node (ref "C3") (pin "1") (pinfunction "1_1") (pintype "passive"))
      (node (ref "C30") (pin "2") (pinfunction "2_2") (pintype "passive"))
      (node (ref "C31") (pin "2") (pinfunction "2_2") (pintype "passive"))
      (node (ref "C32") (pin "2") (pinfunction "2_2") (pintype "passive"))
      (node (ref "C35") (pin "1") (pinfunction "1_1") (pintype "passive"))
      (node (ref "C36") (pin "1") (pinfunction "1_1") (pintype "passive"))
      (node (ref "C37") (pin "1") (pinfunction "1_1") (pintype "passive"))
      (node (ref "C4") (pin "1") (pinfunction "1_1") (pintype "passive"))
      (node (ref "C5") (pin "2") (pinfunction "2_2") (pintype "passive"))
      (node (ref "C6") (pin "2") (pinfunction "2_2") (pintype "passive"))
      (node (ref "C7") (pin "2") (pinfunction "2_2") (pintype "passive"))
      (node (ref "C8") (pin "2") (pinfunction "2_2") (pintype "passive"))
      (node (ref "C9") (pin "1") (pinfunction "1_1") (pintype "passive"))
      (node (ref "IC1") (pin "2") (pinfunction "GND_2") (pintype "bidirectional"))
      (node (ref "IC2") (pin "33") (pinfunction "VSS_33") (pintype "bidirectional"))
      (node (ref "IC3") (pin "12") (pinfunction "GND_12") (pintype "bidirectional"))
      (node (ref "IC3") (pin "2") (pinfunction "A1_2") (pintype "bidirectional"))
      (node (ref "IC3") (pin "21") (pinfunction "A0_21") (pintype "bidirectional"))
      (node (ref "IC3") (pin "3") (pinfunction "A2_3") (pintype "bidirectional"))
      (node (ref "IC4") (pin "12") (pinfunction "GND_12") (pintype "bidirectional"))
      (node (ref "IC4") (pin "2") (pinfunction "A1_2") (pintype "bidirectional"))
      (node (ref "IC4") (pin "3") (pinfunction "A2_3") (pintype "bidirectional"))
      (node (ref "JP1") (pin "1") (pinfunction "1_1") (pintype "passive"))
      (node (ref "JP11") (pin "4") (pinfunction "4_4") (pintype "passive"))
      (node (ref "JP12") (pin "4") (pinfunction "4_4") (pintype "passive"))
      (node (ref "JP13") (pin "4") (pinfunction "4_4") (pintype "passive"))
      (node (ref "JP15") (pin "1") (pinfunction "1_1") (pintype "passive"))
      (node (ref "JP16") (pin "1") (pinfunction "1_1") (pintype "passive"))
      (node (ref "JP17") (pin "1") (pinfunction "1_1") (pintype "passive"))
      (node (ref "JP2") (pin "GND1") (pinfunction "GND_GND1") (pintype "bidirectional"))
      (node (ref "JP2") (pin "SHIELD1") (pinfunction "SHIELD_SHIELD1") (pintype "bidirectional"))
      (node (ref "JP2") (pin "SHIELD2") (pinfunction "SHIELD_SHIELD2") (pintype "bidirectional"))
      (node (ref "JP2") (pin "SHIELD3") (pinfunction "SHIELD_SHIELD3") (pintype "bidirectional"))
      (node (ref "JP3") (pin "4") (pinfunction "4_4") (pintype "passive"))
      (node (ref "JP7") (pin "1") (pinfunction "1_1") (pintype "passive"))
      (node (ref "LCD1") (pin "VSS") (pinfunction "VSS_VSS") (pintype "bidirectional"))
      (node (ref "LED1") (pin "C") (pinfunction "C_C") (pintype "passive"))
      (node (ref "Q3") (pin "2") (pinfunction "E_2") (pintype "passive"))
      (node (ref "Q4") (pin "2") (pinfunction "E_2") (pintype "passive"))
      (node (ref "Q5") (pin "2") (pinfunction "S_2") (pintype "passive"))
      (node (ref "R4") (pin "2") (pinfunction "2_2") (pintype "passive"))
      (node (ref "S1") (pin "2") (pinfunction "2_2") (pintype "passive"))
      (node (ref "S10") (pin "LED-") (pinfunction "2_LED-") (pintype "passive"))
      (node (ref "S10") (pin "NO1") (pinfunction "S_NO1") (pintype "passive"))
      (node (ref "S10") (pin "NO2") (pinfunction "S1_NO2") (pintype "passive"))
      (node (ref "S11") (pin "LED-") (pinfunction "2_LED-") (pintype "passive"))
      (node (ref "S11") (pin "NO1") (pinfunction "S_NO1") (pintype "passive"))
      (node (ref "S11") (pin "NO2") (pinfunction "S1_NO2") (pintype "passive"))
      (node (ref "S12") (pin "1") (pinfunction "1_1") (pintype "passive"))
      (node (ref "S13") (pin "1") (pinfunction "1_1") (pintype "passive"))
      (node (ref "S14") (pin "1") (pinfunction "1_1") (pintype "passive"))
      (node (ref "S2") (pin "GND") (pinfunction "GND_GND") (pintype "bidirectional"))
      (node (ref "S3") (pin "C") (pinfunction "C_C") (pintype "power_in"))
      (node (ref "S4") (pin "LED-") (pinfunction "2_LED-") (pintype "passive"))
      (node (ref "S4") (pin "NO1") (pinfunction "S_NO1") (pintype "passive"))
      (node (ref "S4") (pin "NO2") (pinfunction "S1_NO2") (pintype "passive"))
      (node (ref "S5") (pin "LED-") (pinfunction "2_LED-") (pintype "passive"))
      (node (ref "S5") (pin "NO1") (pinfunction "S_NO1") (pintype "passive"))
      (node (ref "S5") (pin "NO2") (pinfunction "S1_NO2") (pintype "passive"))
      (node (ref "S6") (pin "LED-") (pinfunction "2_LED-") (pintype "passive"))
      (node (ref "S6") (pin "NO1") (pinfunction "S_NO1") (pintype "passive"))
      (node (ref "S6") (pin "NO2") (pinfunction "S1_NO2") (pintype "passive"))
      (node (ref "S7") (pin "LED-") (pinfunction "2_LED-") (pintype "passive"))
      (node (ref "S7") (pin "NO1") (pinfunction "S_NO1") (pintype "passive"))
      (node (ref "S7") (pin "NO2") (pinfunction "S1_NO2") (pintype "passive"))
      (node (ref "S8") (pin "LED-") (pinfunction "2_LED-") (pintype "passive"))
      (node (ref "S8") (pin "NO1") (pinfunction "S_NO1") (pintype "passive"))
      (node (ref "S8") (pin "NO2") (pinfunction "S1_NO2") (pintype "passive"))
      (node (ref "S9") (pin "LED-") (pinfunction "2_LED-") (pintype "passive"))
      (node (ref "S9") (pin "NO1") (pinfunction "S_NO1") (pintype "passive"))
      (node (ref "S9") (pin "NO2") (pinfunction "S1_NO2") (pintype "passive"))
      (node (ref "TP7") (pin "P$1") (pinfunction "1_P$1") (pintype "bidirectional"))
    )
    (net (code "25") (name "INTA") (class "Default")
      (node (ref "IC2") (pin "24") (pinfunction "PIO0.14_24") (pintype "bidirectional"))
      (node (ref "IC3") (pin "1") (pinfunction "INT_1") (pintype "bidirectional"))
      (node (ref "R14") (pin "1") (pinfunction "1_1") (pintype "passive"))
    )
    (net (code "26") (name "INTB") (class "Default")
      (node (ref "IC2") (pin "23") (pinfunction "PIO0.13_23") (pintype "bidirectional"))
      (node (ref "IC4") (pin "1") (pinfunction "INT_1") (pintype "bidirectional"))
      (node (ref "R18") (pin "1") (pinfunction "1_1") (pintype "passive"))
    )
    (net (code "27") (name "MI01") (class "Default")
      (node (ref "IC3") (pin "4") (pinfunction "PO0_4") (pintype "bidirectional"))
      (node (ref "JP7") (pin "3") (pinfunction "3_3") (pintype "passive"))
    )
    (net (code "28") (name "MI02") (class "Default")
      (node (ref "IC3") (pin "5") (pinfunction "PO1_5") (pintype "bidirectional"))
      (node (ref "JP7") (pin "2") (pinfunction "2_2") (pintype "passive"))
    )
    (net (code "29") (name "MI03") (class "Default")
      (node (ref "IC3") (pin "6") (pinfunction "PO2_6") (pintype "bidirectional"))
      (node (ref "JP15") (pin "3") (pinfunction "3_3") (pintype "passive"))
    )
    (net (code "30") (name "MI04") (class "Default")
      (node (ref "IC3") (pin "7") (pinfunction "PO3_7") (pintype "bidirectional"))
      (node (ref "JP15") (pin "2") (pinfunction "2_2") (pintype "passive"))
    )
    (net (code "31") (name "MI05") (class "Default")
      (node (ref "IC3") (pin "8") (pinfunction "PO4_8") (pintype "bidirectional"))
      (node (ref "JP8") (pin "4") (pinfunction "4_4") (pintype "passive"))
    )
    (net (code "32") (name "MI06") (class "Default")
      (node (ref "IC3") (pin "9") (pinfunction "PO5_9") (pintype "bidirectional"))
      (node (ref "JP8") (pin "3") (pinfunction "3_3") (pintype "passive"))
    )
    (net (code "33") (name "MI07") (class "Default")
      (node (ref "IC3") (pin "10") (pinfunction "PO6_10") (pintype "bidirectional"))
      (node (ref "JP16") (pin "3") (pinfunction "3_3") (pintype "passive"))
    )
    (net (code "34") (name "MI08") (class "Default")
      (node (ref "IC3") (pin "11") (pinfunction "PO7_11") (pintype "bidirectional"))
      (node (ref "JP16") (pin "2") (pinfunction "2_2") (pintype "passive"))
    )
    (net (code "35") (name "MI09") (class "Default")
      (node (ref "IC3") (pin "13") (pinfunction "P10_13") (pintype "bidirectional"))
      (node (ref "JP9") (pin "4") (pinfunction "4_4") (pintype "passive"))
    )
    (net (code "36") (name "MI10") (class "Default")
      (node (ref "IC3") (pin "14") (pinfunction "P11_14") (pintype "bidirectional"))
      (node (ref "JP9") (pin "3") (pinfunction "3_3") (pintype "passive"))
    )
    (net (code "37") (name "MI11") (class "Default")
      (node (ref "IC3") (pin "15") (pinfunction "P12_15") (pintype "bidirectional"))
      (node (ref "JP17") (pin "3") (pinfunction "3_3") (pintype "passive"))
    )
    (net (code "38") (name "MI12") (class "Default")
      (node (ref "IC3") (pin "16") (pinfunction "P13_16") (pintype "bidirectional"))
      (node (ref "JP17") (pin "2") (pinfunction "2_2") (pintype "passive"))
    )
    (net (code "39") (name "MI13") (class "Default")
      (node (ref "C32") (pin "1") (pinfunction "1_1") (pintype "passive"))
      (node (ref "IC3") (pin "17") (pinfunction "P14_17") (pintype "bidirectional"))
      (node (ref "R27") (pin "1") (pinfunction "1_1") (pintype "passive"))
      (node (ref "S11") (pin "C1") (pinfunction "P_C1") (pintype "passive"))
      (node (ref "S11") (pin "C2") (pinfunction "P1_C2") (pintype "passive"))
    )
    (net (code "40") (name "MI14") (class "Default")
      (node (ref "IC3") (pin "18") (pinfunction "P15_18") (pintype "bidirectional"))
      (node (ref "S11") (pin "LED+") (pinfunction "1_LED+") (pintype "passive"))
    )
    (net (code "41") (name "MI15") (class "Default")
      (node (ref "IC3") (pin "19") (pinfunction "P16_19") (pintype "bidirectional"))
    )
    (net (code "42") (name "MI16") (class "Default")
      (node (ref "IC3") (pin "20") (pinfunction "P17_20") (pintype "bidirectional"))
    )
    (net (code "43") (name "MI18") (class "Default")
      (node (ref "C15") (pin "2") (pinfunction "2_2") (pintype "passive"))
      (node (ref "IC4") (pin "4") (pinfunction "PO0_4") (pintype "bidirectional"))
      (node (ref "R15") (pin "2") (pinfunction "2_2") (pintype "passive"))
      (node (ref "S3") (pin "1") (pinfunction "1_1") (pintype "input"))
    )
    (net (code "44") (name "MI19") (class "Default")
      (node (ref "C16") (pin "2") (pinfunction "2_2") (pintype "passive"))
      (node (ref "IC4") (pin "5") (pinfunction "PO1_5") (pintype "bidirectional"))
      (node (ref "R16") (pin "2") (pinfunction "2_2") (pintype "passive"))
      (node (ref "S3") (pin "T") (pinfunction "T_T") (pintype "input"))
    )
    (net (code "45") (name "MI20") (class "Default")
      (node (ref "C17") (pin "2") (pinfunction "2_2") (pintype "passive"))
      (node (ref "IC4") (pin "6") (pinfunction "PO2_6") (pintype "bidirectional"))
      (node (ref "R17") (pin "2") (pinfunction "2_2") (pintype "passive"))
      (node (ref "S3") (pin "2") (pinfunction "2_2") (pintype "input"))
    )
    (net (code "46") (name "MI21") (class "Default")
      (node (ref "IC4") (pin "7") (pinfunction "PO3_7") (pintype "bidirectional"))
      (node (ref "JP10") (pin "4") (pinfunction "4_4") (pintype "passive"))
    )
    (net (code "47") (name "MI22") (class "Default")
      (node (ref "IC4") (pin "8") (pinfunction "PO4_8") (pintype "bidirectional"))
      (node (ref "JP10") (pin "3") (pinfunction "3_3") (pintype "passive"))
    )
    (net (code "48") (name "MI23") (class "Default")
      (node (ref "IC4") (pin "9") (pinfunction "PO5_9") (pintype "bidirectional"))
      (node (ref "JP10") (pin "2") (pinfunction "2_2") (pintype "passive"))
    )
    (net (code "49") (name "MI24") (class "Default")
      (node (ref "IC4") (pin "10") (pinfunction "PO6_10") (pintype "bidirectional"))
      (node (ref "JP10") (pin "1") (pinfunction "1_1") (pintype "passive"))
    )
    (net (code "50") (name "MI25") (class "Default")
      (node (ref "IC4") (pin "11") (pinfunction "PO7_11") (pintype "bidirectional"))
      (node (ref "JP18") (pin "4") (pinfunction "4_4") (pintype "passive"))
    )
    (net (code "51") (name "MI26") (class "Default")
      (node (ref "C35") (pin "2") (pinfunction "2_2") (pintype "passive"))
      (node (ref "IC4") (pin "13") (pinfunction "P10_13") (pintype "bidirectional"))
      (node (ref "R31") (pin "1") (pinfunction "1_1") (pintype "passive"))
      (node (ref "S12") (pin "2") (pinfunction "2_2") (pintype "passive"))
    )
    (net (code "52") (name "MI27") (class "Default")
      (node (ref "C36") (pin "2") (pinfunction "2_2") (pintype "passive"))
      (node (ref "IC4") (pin "14") (pinfunction "P11_14") (pintype "bidirectional"))
      (node (ref "R32") (pin "1") (pinfunction "1_1") (pintype "passive"))
      (node (ref "S13") (pin "2") (pinfunction "2_2") (pintype "passive"))
    )
    (net (code "53") (name "MI28") (class "Default")
      (node (ref "C37") (pin "2") (pinfunction "2_2") (pintype "passive"))
      (node (ref "IC4") (pin "15") (pinfunction "P12_15") (pintype "bidirectional"))
      (node (ref "R33") (pin "1") (pinfunction "1_1") (pintype "passive"))
      (node (ref "S14") (pin "2") (pinfunction "2_2") (pintype "passive"))
    )
    (net (code "54") (name "MI29") (class "Default")
      (node (ref "IC4") (pin "16") (pinfunction "P13_16") (pintype "bidirectional"))
    )
    (net (code "55") (name "MI30") (class "Default")
      (node (ref "IC4") (pin "17") (pinfunction "P14_17") (pintype "bidirectional"))
    )
    (net (code "56") (name "MI31") (class "Default")
      (node (ref "IC4") (pin "18") (pinfunction "P15_18") (pintype "bidirectional"))
    )
    (net (code "57") (name "MI32") (class "Default")
      (node (ref "C19") (pin "1") (pinfunction "1_1") (pintype "passive"))
      (node (ref "IC4") (pin "19") (pinfunction "P16_19") (pintype "bidirectional"))
      (node (ref "R19") (pin "1") (pinfunction "1_1") (pintype "passive"))
      (node (ref "S4") (pin "C1") (pinfunction "P_C1") (pintype "passive"))
      (node (ref "S4") (pin "C2") (pinfunction "P1_C2") (pintype "passive"))
    )
    (net (code "58") (name "MI33") (class "Default")
      (node (ref "IC4") (pin "20") (pinfunction "P17_20") (pintype "bidirectional"))
      (node (ref "S4") (pin "LED+") (pinfunction "1_LED+") (pintype "passive"))
    )
    (net (code "59") (name "Net-(C33-Pad2)") (class "Default")
      (node (ref "C33") (pin "2") (pinfunction "2_2") (pintype "passive"))
      (node (ref "LCD1") (pin "VOUT") (pinfunction "VOUT_VOUT") (pintype "bidirectional"))
    )
    (net (code "60") (name "Net-(C34-Pad1)") (class "Default")
      (node (ref "C34") (pin "1") (pinfunction "1_1") (pintype "passive"))
      (node (ref "LCD1") (pin "CAP1P") (pinfunction "CAP1P_CAP1P") (pintype "bidirectional"))
    )
    (net (code "61") (name "Net-(D1-PadA)") (class "Default")
      (node (ref "D1") (pin "A") (pinfunction "A_A") (pintype "passive"))
      (node (ref "F1") (pin "1") (pinfunction "1_1") (pintype "bidirectional"))
    )
    (net (code "62") (name "Net-(IC2-PIO0.3)") (class "Default")
      (node (ref "IC2") (pin "9") (pinfunction "PIO0.3_9") (pintype "bidirectional"))
      (node (ref "R3") (pin "2") (pinfunction "2_2") (pintype "passive"))
      (node (ref "R4") (pin "1") (pinfunction "1_1") (pintype "passive"))
    )
    (net (code "63") (name "Net-(IC2-PIO0.6)") (class "Default")
      (node (ref "IC2") (pin "15") (pinfunction "PIO0.6_15") (pintype "bidirectional"))
      (node (ref "Q2") (pin "1") (pinfunction "G_1") (pintype "passive"))
    )
    (net (code "64") (name "Net-(IC2-USB.D+)") (class "Default")
      (node (ref "IC2") (pin "14") (pinfunction "USB.D+_14") (pintype "bidirectional"))
      (node (ref "R5") (pin "2") (pinfunction "2_2") (pintype "passive"))
      (node (ref "R7") (pin "2") (pinfunction "2_2") (pintype "passive"))
    )
    (net (code "65") (name "Net-(IC2-USB.D-)") (class "Default")
      (node (ref "IC2") (pin "13") (pinfunction "USB.D-_13") (pintype "bidirectional"))
      (node (ref "R6") (pin "2") (pinfunction "2_2") (pintype "passive"))
    )
    (net (code "66") (name "Net-(JP2-VCC)") (class "Default")
      (node (ref "F1") (pin "2") (pinfunction "2_2") (pintype "bidirectional"))
      (node (ref "JP2") (pin "VBUS1") (pinfunction "VCC_VBUS1") (pintype "bidirectional"))
    )
    (net (code "67") (name "Net-(LCD1-CAP1N)") (class "Default")
      (node (ref "C34") (pin "2") (pinfunction "2_2") (pintype "passive"))
      (node (ref "LCD1") (pin "CAPN") (pinfunction "CAP1N_CAPN") (pintype "bidirectional"))
    )
    (net (code "68") (name "Net-(LCD1-PadRST)") (class "Default")
      (node (ref "LCD1") (pin "RST") (pinfunction "RST_RST") (pintype "bidirectional"))
      (node (ref "R28") (pin "1") (pinfunction "1_1") (pintype "passive"))
    )
    (net (code "69") (name "Net-(LED1-PadA)") (class "Default")
      (node (ref "LED1") (pin "A") (pinfunction "A_A") (pintype "passive"))
      (node (ref "R30") (pin "1") (pinfunction "1_1") (pintype "passive"))
    )
    (net (code "70") (name "Net-(Q2-D)") (class "Default")
      (node (ref "Q2") (pin "3") (pinfunction "D_3") (pintype "passive"))
      (node (ref "R5") (pin "1") (pinfunction "1_1") (pintype "passive"))
    )
    (net (code "71") (name "Net-(Q3-B)") (class "Default")
      (node (ref "Q3") (pin "1") (pinfunction "B_1") (pintype "passive"))
      (node (ref "R8") (pin "2") (pinfunction "2_2") (pintype "passive"))
    )
    (net (code "72") (name "Net-(Q3-C)") (class "Default")
      (node (ref "Q3") (pin "3") (pinfunction "C_3") (pintype "passive"))
      (node (ref "SG1") (pin "-") (pinfunction "2_-") (pintype "passive"))
    )
    (net (code "73") (name "Net-(Q4-B)") (class "Default")
      (node (ref "Q4") (pin "1") (pinfunction "B_1") (pintype "passive"))
      (node (ref "R20") (pin "2") (pinfunction "2_2") (pintype "passive"))
    )
    (net (code "74") (name "Net-(Q4-C)") (class "Default")
      (node (ref "D2") (pin "A") (pinfunction "A_A") (pintype "passive"))
      (node (ref "MOT1") (pin "-") (pinfunction "-_-") (pintype "bidirectional"))
      (node (ref "Q4") (pin "3") (pinfunction "C_3") (pintype "passive"))
    )
    (net (code "75") (name "Net-(Q5-G)") (class "Default")
      (node (ref "Q5") (pin "1") (pinfunction "G_1") (pintype "passive"))
      (node (ref "R29") (pin "2") (pinfunction "2_2") (pintype "passive"))
    )
    (net (code "76") (name "Net-(R1-Pad2)") (class "Default")
      (node (ref "R1") (pin "2") (pinfunction "2_2") (pintype "passive"))
      (node (ref "R2") (pin "2") (pinfunction "2_2") (pintype "passive"))
      (node (ref "SJ1") (pin "2") (pinfunction "2_2") (pintype "passive"))
    )
    (net (code "77") (name "PROGR") (class "Default")
      (node (ref "IC2") (pin "3") (pinfunction "PIO0.1_3") (pintype "bidirectional"))
      (node (ref "S1") (pin "1") (pinfunction "1_1") (pintype "passive"))
    )
    (net (code "78") (name "RX") (class "Default")
      (node (ref "TP6") (pin "P$1") (pinfunction "1_P$1") (pintype "bidirectional"))
    )
    (net (code "79") (name "SCL") (class "Default")
      (node (ref "IC2") (pin "10") (pinfunction "PIO0.4_10") (pintype "bidirectional"))
      (node (ref "IC3") (pin "22") (pinfunction "SCL_22") (pintype "bidirectional"))
      (node (ref "IC4") (pin "22") (pinfunction "SCL_22") (pintype "bidirectional"))
      (node (ref "JP1") (pin "2") (pinfunction "2_2") (pintype "passive"))
      (node (ref "LCD1") (pin "SCL") (pinfunction "SCL_SCL") (pintype "bidirectional"))
      (node (ref "R2") (pin "1") (pinfunction "1_1") (pintype "passive"))
      (node (ref "TP4") (pin "P$1") (pinfunction "1_P$1") (pintype "bidirectional"))
    )
    (net (code "80") (name "SDA") (class "Default")
      (node (ref "IC2") (pin "11") (pinfunction "PIO0.5_11") (pintype "bidirectional"))
      (node (ref "IC3") (pin "23") (pinfunction "SDA_23") (pintype "bidirectional"))
      (node (ref "IC4") (pin "23") (pinfunction "SDA_23") (pintype "bidirectional"))
      (node (ref "JP1") (pin "3") (pinfunction "3_3") (pintype "passive"))
      (node (ref "LCD1") (pin "SDA") (pinfunction "SDA_SDA") (pintype "bidirectional"))
      (node (ref "R1") (pin "1") (pinfunction "1_1") (pintype "passive"))
      (node (ref "TP3") (pin "P$1") (pinfunction "1_P$1") (pintype "bidirectional"))
    )
    (net (code "81") (name "TX") (class "Default")
      (node (ref "TP5") (pin "P$1") (pinfunction "1_P$1") (pintype "bidirectional"))
    )
    (net (code "82") (name "VCC") (class "Default")
      (node (ref "C1") (pin "2") (pinfunction "2_2") (pintype "passive"))
      (node (ref "C2") (pin "2") (pinfunction "2_2") (pintype "passive"))
      (node (ref "D1") (pin "C") (pinfunction "C_C") (pintype "passive"))
      (node (ref "IC1") (pin "1") (pinfunction "VIN_1") (pintype "bidirectional"))
      (node (ref "IC1") (pin "3") (pinfunction "EN_3") (pintype "bidirectional"))
      (node (ref "R3") (pin "1") (pinfunction "1_1") (pintype "passive"))
      (node (ref "TP2") (pin "P$1") (pinfunction "1_P$1") (pintype "bidirectional"))
    )
    (net (code "83") (name "VIB") (class "Default")
      (node (ref "IC2") (pin "21") (pinfunction "PIO0.11_21") (pintype "bidirectional"))
      (node (ref "R20") (pin "1") (pinfunction "1_1") (pintype "passive"))
    )
    (net (code "84") (name "XTALIN") (class "Default")
      (node (ref "C7") (pin "1") (pinfunction "1_1") (pintype "passive"))
      (node (ref "IC2") (pin "4") (pinfunction "XTALIN_4") (pintype "bidirectional"))
      (node (ref "Q1") (pin "3") (pinfunction "P$2_3") (pintype "passive"))
    )
    (net (code "85") (name "XTALOUT") (class "Default")
      (node (ref "C8") (pin "1") (pinfunction "1_1") (pintype "passive"))
      (node (ref "IC2") (pin "5") (pinfunction "XTALOUT_5") (pintype "bidirectional"))
      (node (ref "Q1") (pin "1") (pinfunction "P$1_1") (pintype "passive"))
    )
    (net (code "86") (name "unconnected-(IC1-NC{slash}ADJ-Pad4)") (class "Default")
      (node (ref "IC1") (pin "4") (pinfunction "NC/ADJ_4") (pintype "bidirectional"))
    )
    (net (code "87") (name "unconnected-(IC2-PIO0.0-Pad2)") (class "Default")
      (node (ref "IC2") (pin "2") (pinfunction "PIO0.0_2") (pintype "bidirectional"))
    )
    (net (code "88") (name "unconnected-(IC2-PIO0.2-Pad8)") (class "Default")
      (node (ref "IC2") (pin "8") (pinfunction "PIO0.2_8") (pintype "bidirectional"))
    )
    (net (code "89") (name "unconnected-(IC2-PIO0.7-Pad16)") (class "Default")
      (node (ref "IC2") (pin "16") (pinfunction "PIO0.7_16") (pintype "bidirectional"))
    )
    (net (code "90") (name "unconnected-(IC2-PIO0.8-Pad17)") (class "Default")
      (node (ref "IC2") (pin "17") (pinfunction "PIO0.8_17") (pintype "bidirectional"))
    )
    (net (code "91") (name "unconnected-(IC2-PIO0.9-Pad18)") (class "Default")
      (node (ref "IC2") (pin "18") (pinfunction "PIO0.9_18") (pintype "bidirectional"))
    )
    (net (code "92") (name "unconnected-(IC2-PIO0.10-Pad19)") (class "Default")
      (node (ref "IC2") (pin "19") (pinfunction "PIO0.10_19") (pintype "bidirectional"))
    )
    (net (code "93") (name "unconnected-(IC2-PIO0.15-Pad25)") (class "Default")
      (node (ref "IC2") (pin "25") (pinfunction "PIO0.15_25") (pintype "bidirectional"))
    )
    (net (code "94") (name "unconnected-(IC2-PIO0.16-Pad26)") (class "Default")
      (node (ref "IC2") (pin "26") (pinfunction "PIO0.16_26") (pintype "bidirectional"))
    )
    (net (code "95") (name "unconnected-(IC2-PIO0.17-Pad30)") (class "Default")
      (node (ref "IC2") (pin "30") (pinfunction "PIO0.17_30") (pintype "bidirectional"))
    )
    (net (code "96") (name "unconnected-(IC2-PIO0.18-Pad31)") (class "Default")
      (node (ref "IC2") (pin "31") (pinfunction "PIO0.18_31") (pintype "bidirectional"))
    )
    (net (code "97") (name "unconnected-(IC2-PIO0.19-Pad32)") (class "Default")
      (node (ref "IC2") (pin "32") (pinfunction "PIO0.19_32") (pintype "bidirectional"))
    )
    (net (code "98") (name "unconnected-(IC2-PIO0.20-Pad7)") (class "Default")
      (node (ref "IC2") (pin "7") (pinfunction "PIO0.20_7") (pintype "bidirectional"))
    )
    (net (code "99") (name "unconnected-(IC2-PIO0.21-Pad12)") (class "Default")
      (node (ref "IC2") (pin "12") (pinfunction "PIO0.21_12") (pintype "bidirectional"))
    )
    (net (code "100") (name "unconnected-(IC2-PIO0.23-Pad27)") (class "Default")
      (node (ref "IC2") (pin "27") (pinfunction "PIO0.23_27") (pintype "bidirectional"))
    )
    (net (code "101") (name "unconnected-(IC2-PIO1.15-Pad28)") (class "Default")
      (node (ref "IC2") (pin "28") (pinfunction "PIO1.15_28") (pintype "bidirectional"))
    )
    (net (code "102") (name "unconnected-(IC2-PIO1.19-Pad1)") (class "Default")
      (node (ref "IC2") (pin "1") (pinfunction "PIO1.19_1") (pintype "bidirectional"))
    )
    (net (code "103") (name "unconnected-(JP2-ID-PadID1)") (class "Default")
      (node (ref "JP2") (pin "ID1") (pinfunction "ID_ID1") (pintype "bidirectional"))
    )
    (net (code "104") (name "unconnected-(JP4-Pad3)") (class "Default")
      (node (ref "JP4") (pin "3") (pinfunction "3_3") (pintype "passive"))
    )
    (net (code "105") (name "unconnected-(JP4-Pad4)") (class "Default")
      (node (ref "JP4") (pin "4") (pinfunction "4_4") (pintype "passive"))
    )
    (net (code "106") (name "unconnected-(JP5-Pad3)") (class "Default")
      (node (ref "JP5") (pin "3") (pinfunction "3_3") (pintype "passive"))
    )
    (net (code "107") (name "unconnected-(JP5-Pad4)") (class "Default")
      (node (ref "JP5") (pin "4") (pinfunction "4_4") (pintype "passive"))
    )
    (net (code "108") (name "unconnected-(JP8-Pad1)") (class "Default")
      (node (ref "JP8") (pin "1") (pinfunction "1_1") (pintype "passive"))
    )
    (net (code "109") (name "unconnected-(JP8-Pad2)") (class "Default")
      (node (ref "JP8") (pin "2") (pinfunction "2_2") (pintype "passive"))
    )
    (net (code "110") (name "unconnected-(JP9-Pad1)") (class "Default")
      (node (ref "JP9") (pin "1") (pinfunction "1_1") (pintype "passive"))
    )
    (net (code "111") (name "unconnected-(JP9-Pad2)") (class "Default")
      (node (ref "JP9") (pin "2") (pinfunction "2_2") (pintype "passive"))
    )
    (net (code "112") (name "unconnected-(JP14-Pad2)") (class "Default")
      (node (ref "JP14") (pin "2") (pinfunction "2_2") (pintype "passive"))
    )
    (net (code "113") (name "unconnected-(JP14-Pad3)") (class "Default")
      (node (ref "JP14") (pin "3") (pinfunction "3_3") (pintype "passive"))
    )
    (net (code "114") (name "unconnected-(JP14-Pad4)") (class "Default")
      (node (ref "JP14") (pin "4") (pinfunction "4_4") (pintype "passive"))
    )
    (net (code "115") (name "unconnected-(JP18-Pad1)") (class "Default")
      (node (ref "JP18") (pin "1") (pinfunction "1_1") (pintype "passive"))
    )
    (net (code "116") (name "unconnected-(JP18-Pad2)") (class "Default")
      (node (ref "JP18") (pin "2") (pinfunction "2_2") (pintype "passive"))
    )
    (net (code "117") (name "unconnected-(JP18-Pad3)") (class "Default")
      (node (ref "JP18") (pin "3") (pinfunction "3_3") (pintype "passive"))
    )
    (net (code "118") (name "unconnected-(S4-O-PadNC1)") (class "Default")
      (node (ref "S4") (pin "NC1") (pinfunction "O_NC1") (pintype "passive"))
    )
    (net (code "119") (name "unconnected-(S4-O1-PadNC2)") (class "Default")
      (node (ref "S4") (pin "NC2") (pinfunction "O1_NC2") (pintype "passive"))
    )
    (net (code "120") (name "unconnected-(S5-O-PadNC1)") (class "Default")
      (node (ref "S5") (pin "NC1") (pinfunction "O_NC1") (pintype "passive"))
    )
    (net (code "121") (name "unconnected-(S5-O1-PadNC2)") (class "Default")
      (node (ref "S5") (pin "NC2") (pinfunction "O1_NC2") (pintype "passive"))
    )
    (net (code "122") (name "unconnected-(S6-O-PadNC1)") (class "Default")
      (node (ref "S6") (pin "NC1") (pinfunction "O_NC1") (pintype "passive"))
    )
    (net (code "123") (name "unconnected-(S6-O1-PadNC2)") (class "Default")
      (node (ref "S6") (pin "NC2") (pinfunction "O1_NC2") (pintype "passive"))
    )
    (net (code "124") (name "unconnected-(S7-O-PadNC1)") (class "Default")
      (node (ref "S7") (pin "NC1") (pinfunction "O_NC1") (pintype "passive"))
    )
    (net (code "125") (name "unconnected-(S7-O1-PadNC2)") (class "Default")
      (node (ref "S7") (pin "NC2") (pinfunction "O1_NC2") (pintype "passive"))
    )
    (net (code "126") (name "unconnected-(S8-O-PadNC1)") (class "Default")
      (node (ref "S8") (pin "NC1") (pinfunction "O_NC1") (pintype "passive"))
    )
    (net (code "127") (name "unconnected-(S8-O1-PadNC2)") (class "Default")
      (node (ref "S8") (pin "NC2") (pinfunction "O1_NC2") (pintype "passive"))
    )
    (net (code "128") (name "unconnected-(S9-O-PadNC1)") (class "Default")
      (node (ref "S9") (pin "NC1") (pinfunction "O_NC1") (pintype "passive"))
    )
    (net (code "129") (name "unconnected-(S9-O1-PadNC2)") (class "Default")
      (node (ref "S9") (pin "NC2") (pinfunction "O1_NC2") (pintype "passive"))
    )
    (net (code "130") (name "unconnected-(S10-O-PadNC1)") (class "Default")
      (node (ref "S10") (pin "NC1") (pinfunction "O_NC1") (pintype "passive"))
    )
    (net (code "131") (name "unconnected-(S10-O1-PadNC2)") (class "Default")
      (node (ref "S10") (pin "NC2") (pinfunction "O1_NC2") (pintype "passive"))
    )
    (net (code "132") (name "unconnected-(S11-O-PadNC1)") (class "Default")
      (node (ref "S11") (pin "NC1") (pinfunction "O_NC1") (pintype "passive"))
    )
    (net (code "133") (name "unconnected-(S11-O1-PadNC2)") (class "Default")
      (node (ref "S11") (pin "NC2") (pinfunction "O1_NC2") (pintype "passive"))
    )
  )
)
